# MK-312BT_V1_3B.net
KiCad netlist of a schematic drawn in EAGLE
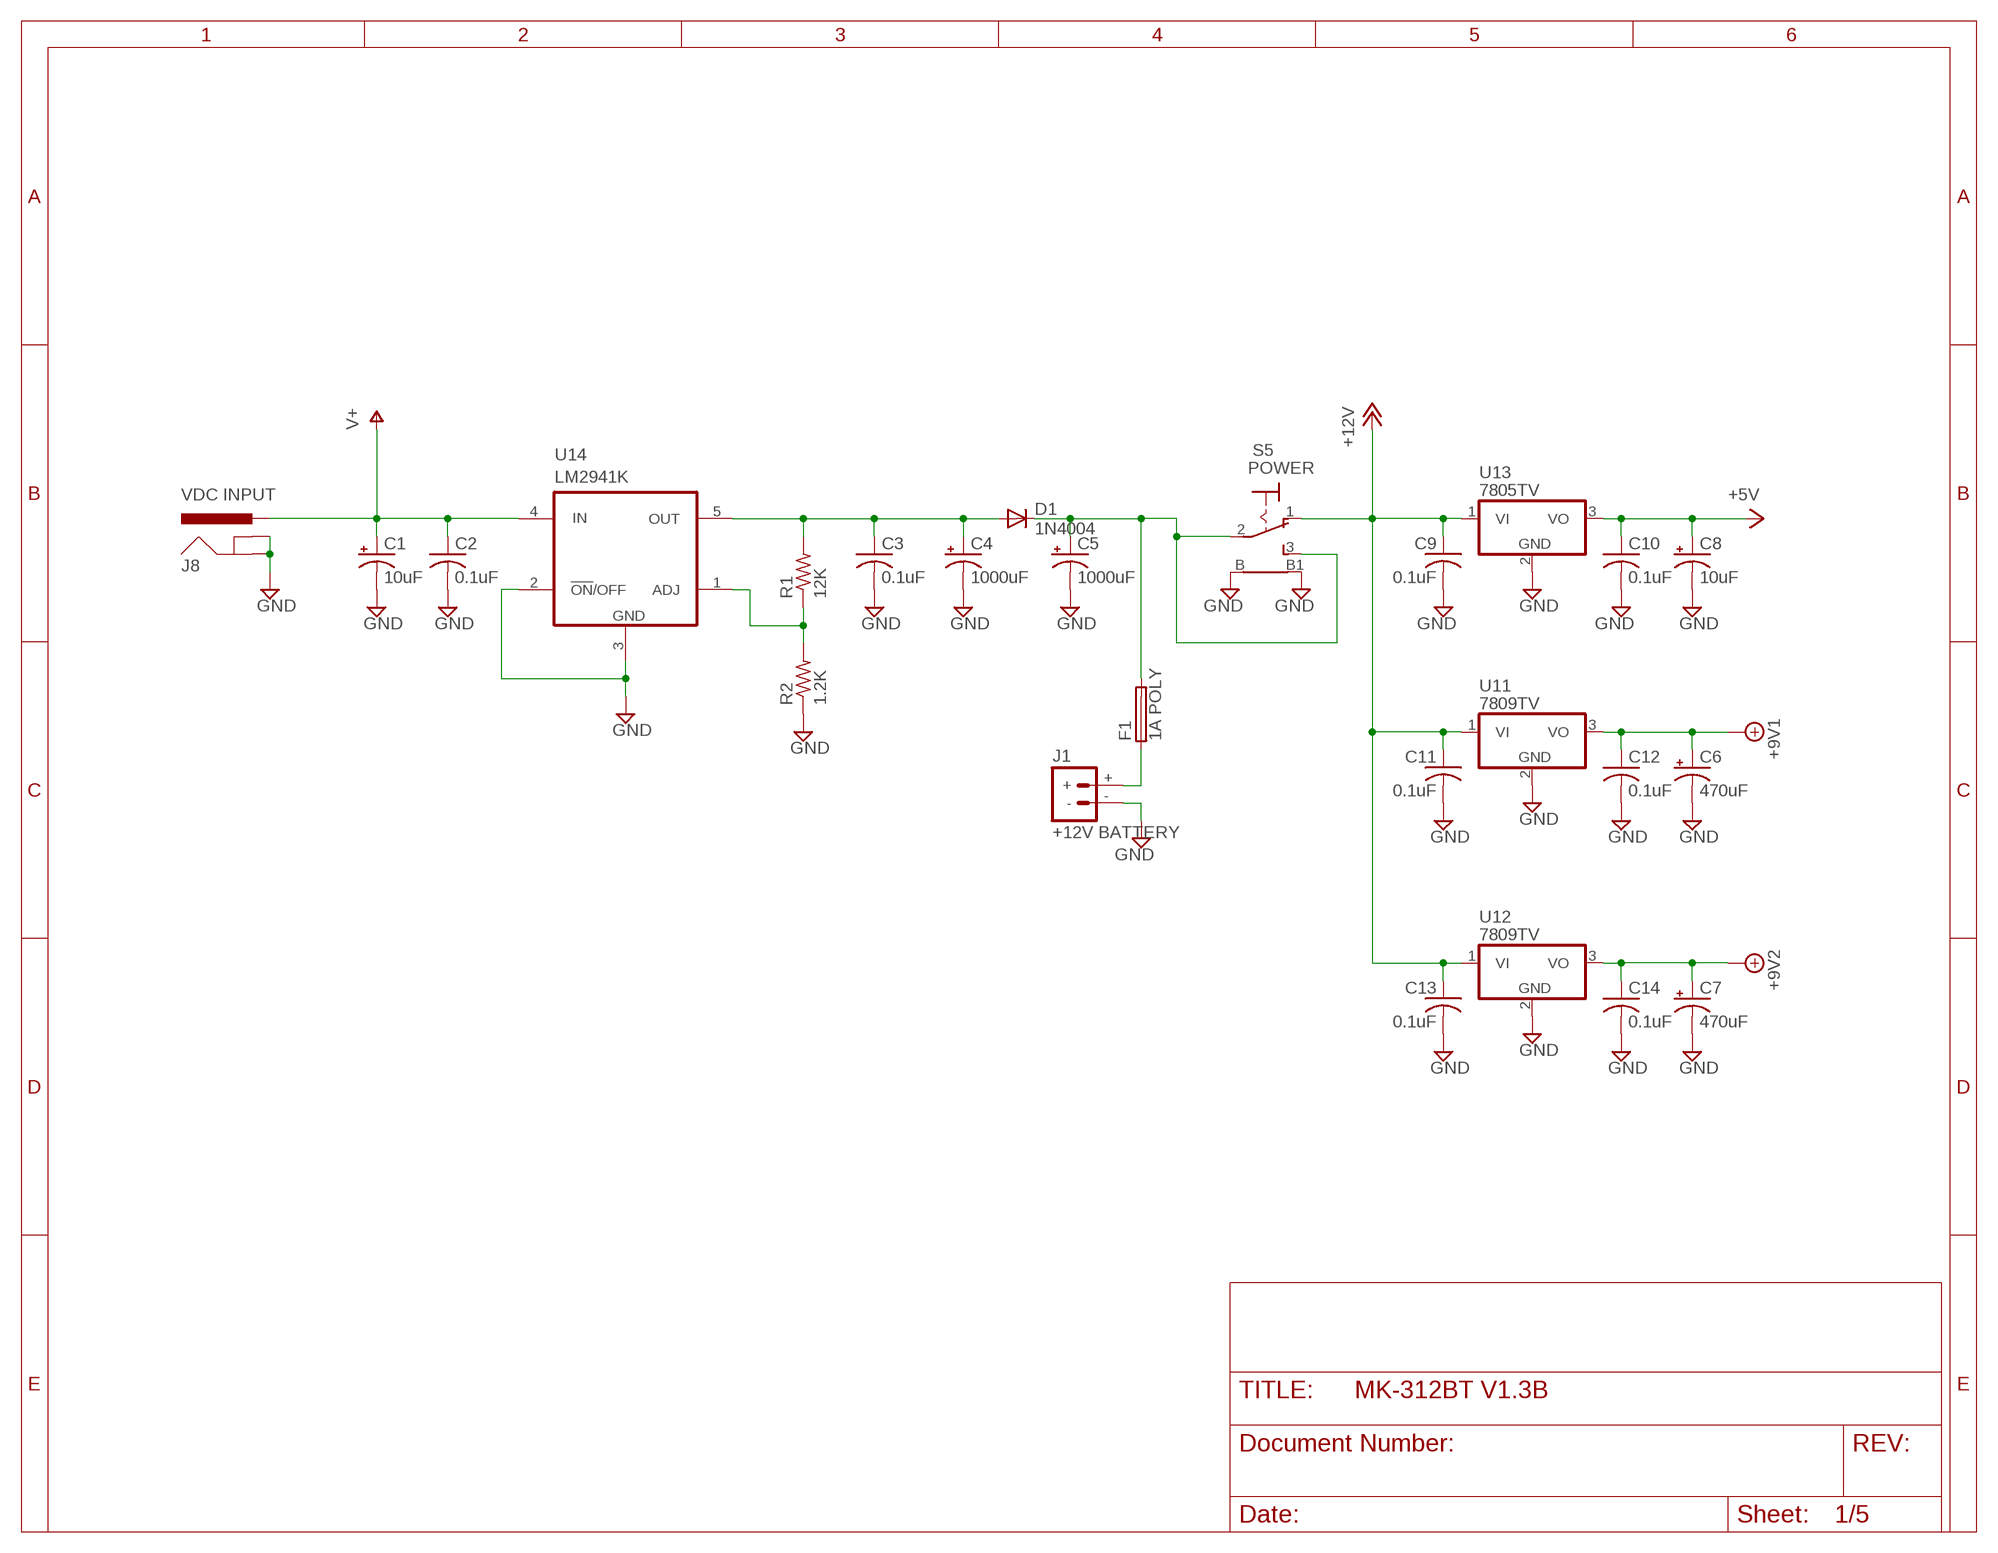
[diagram p0: schematic, sheet 1]
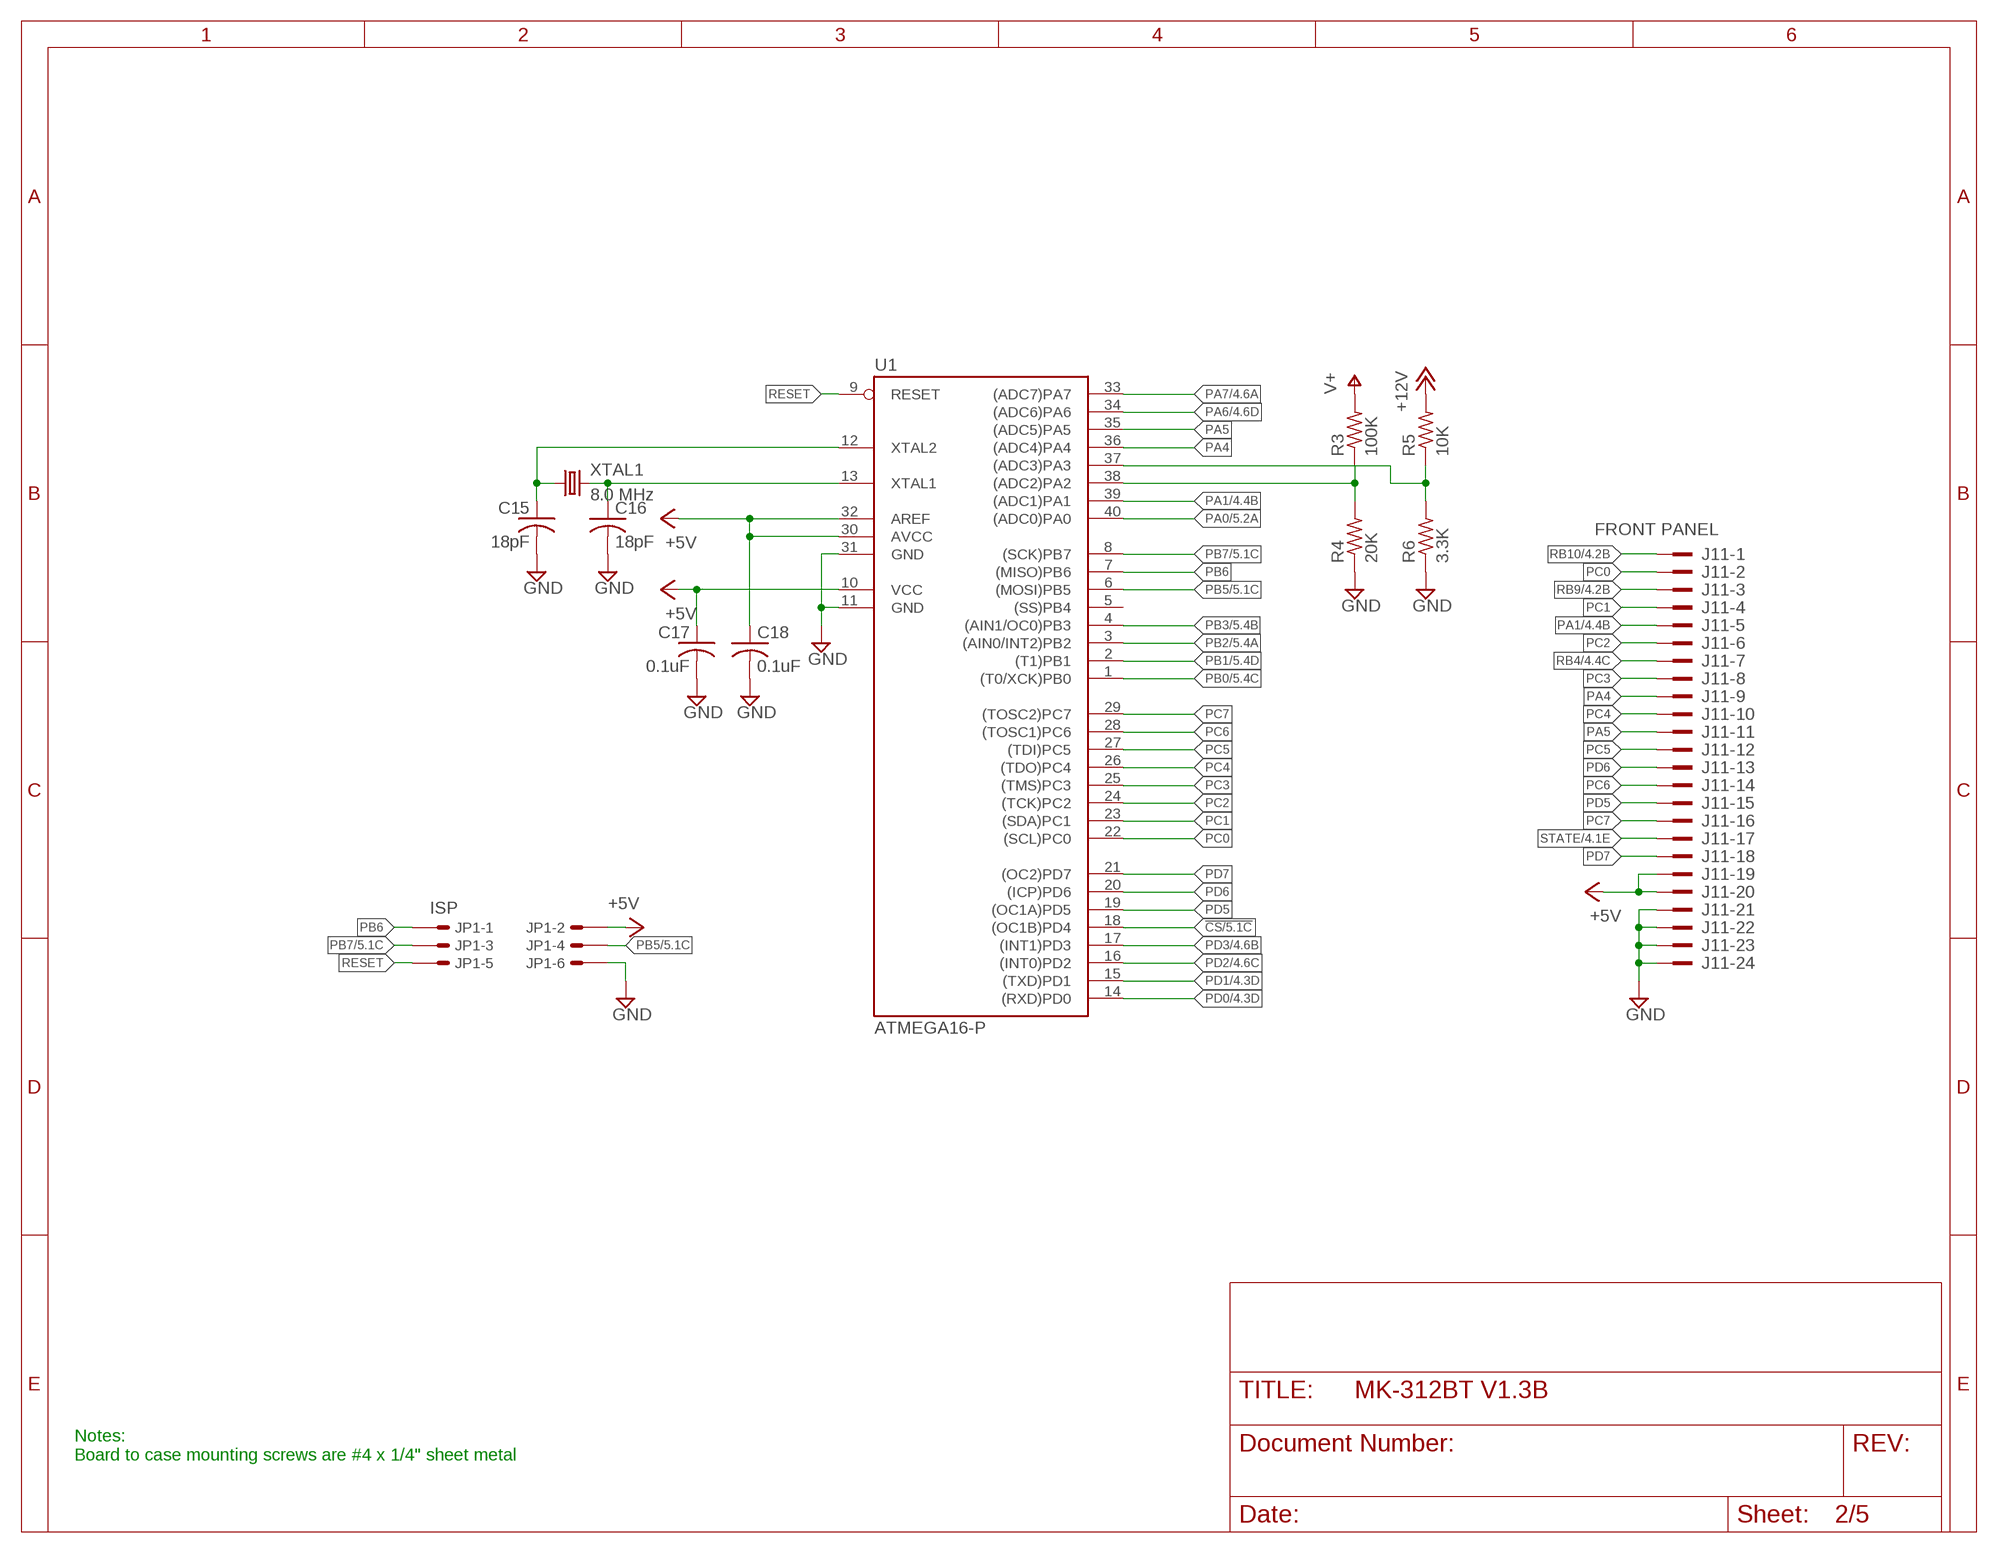
[diagram p1: schematic, sheet 2]
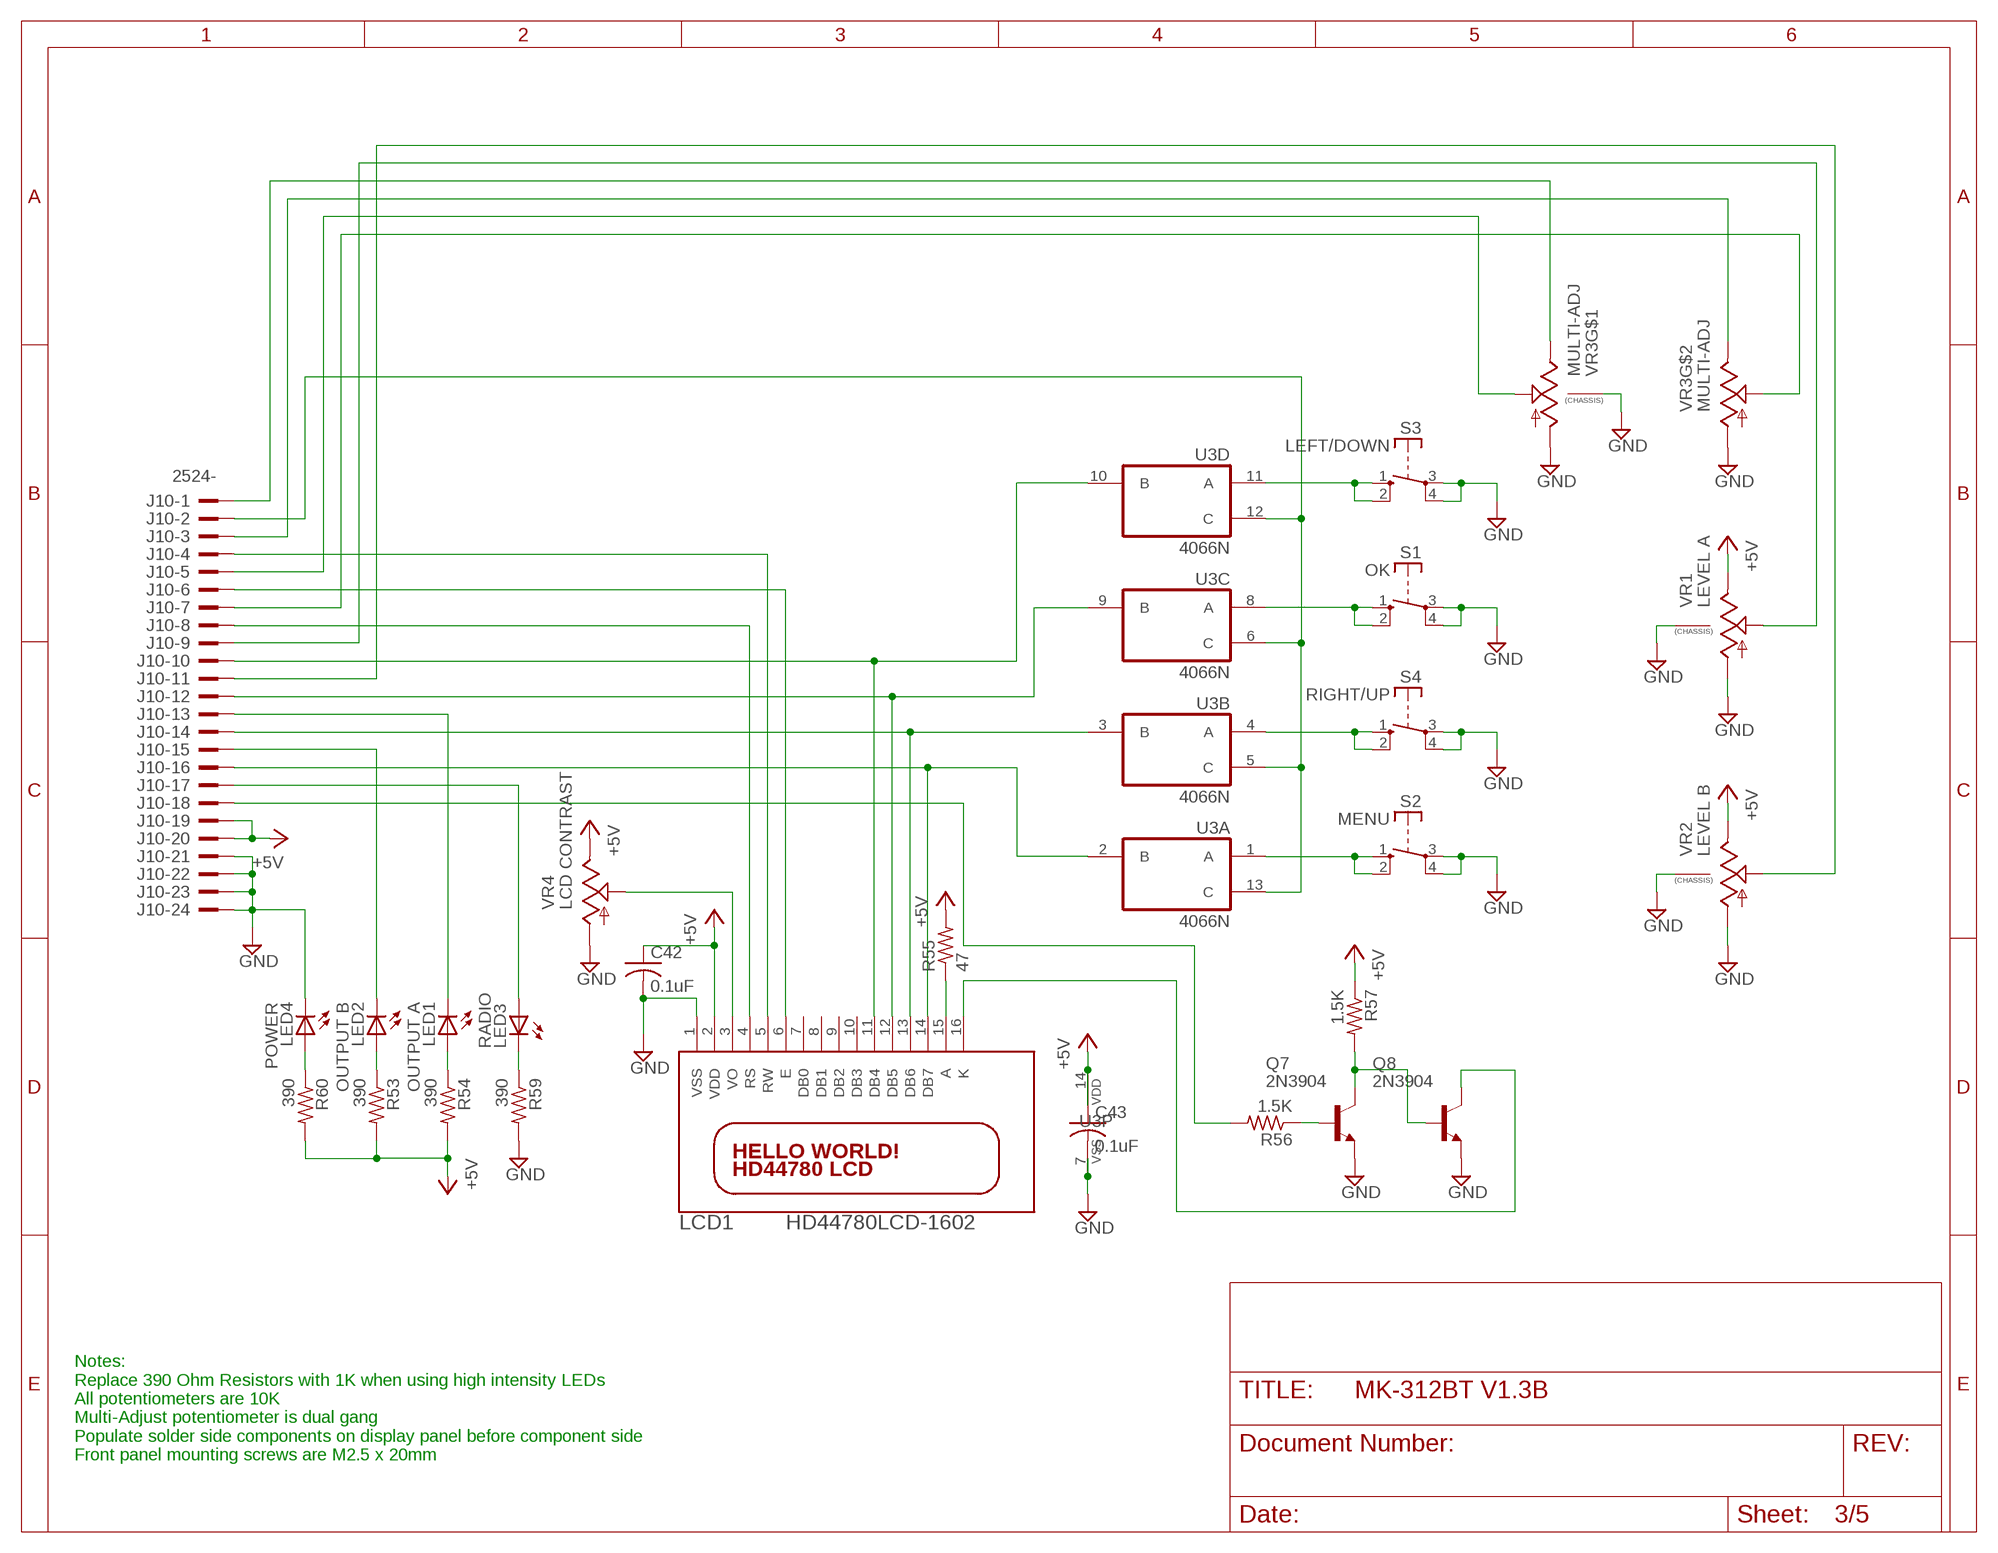
[diagram p2: schematic, sheet 3]
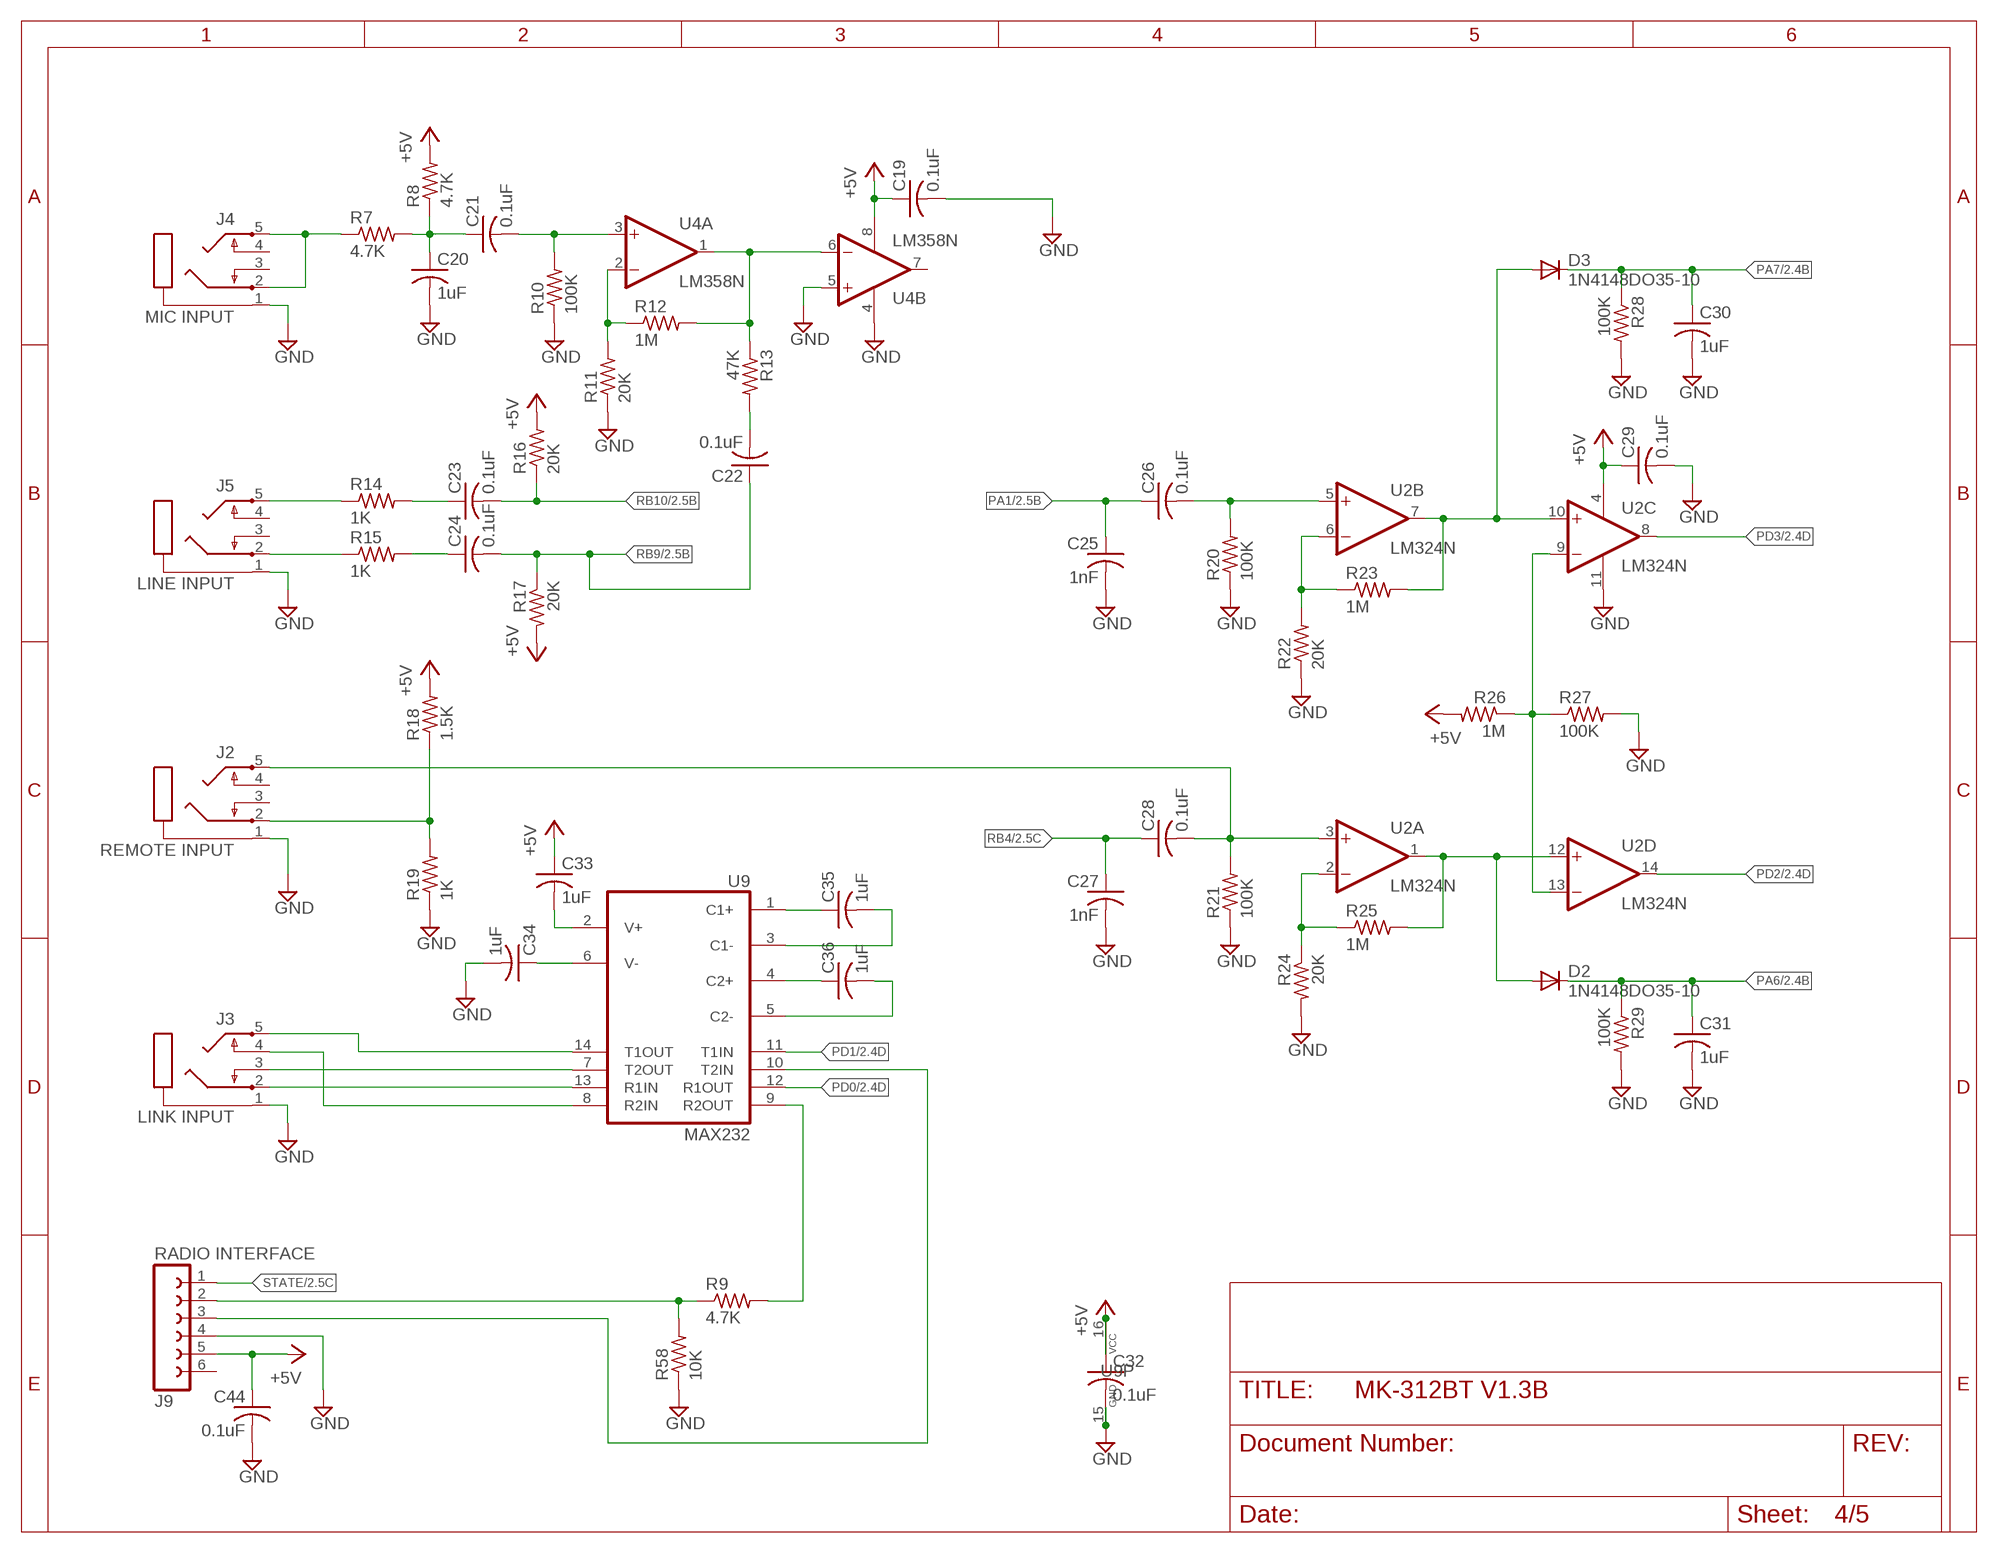
[diagram p3: schematic, sheet 4]
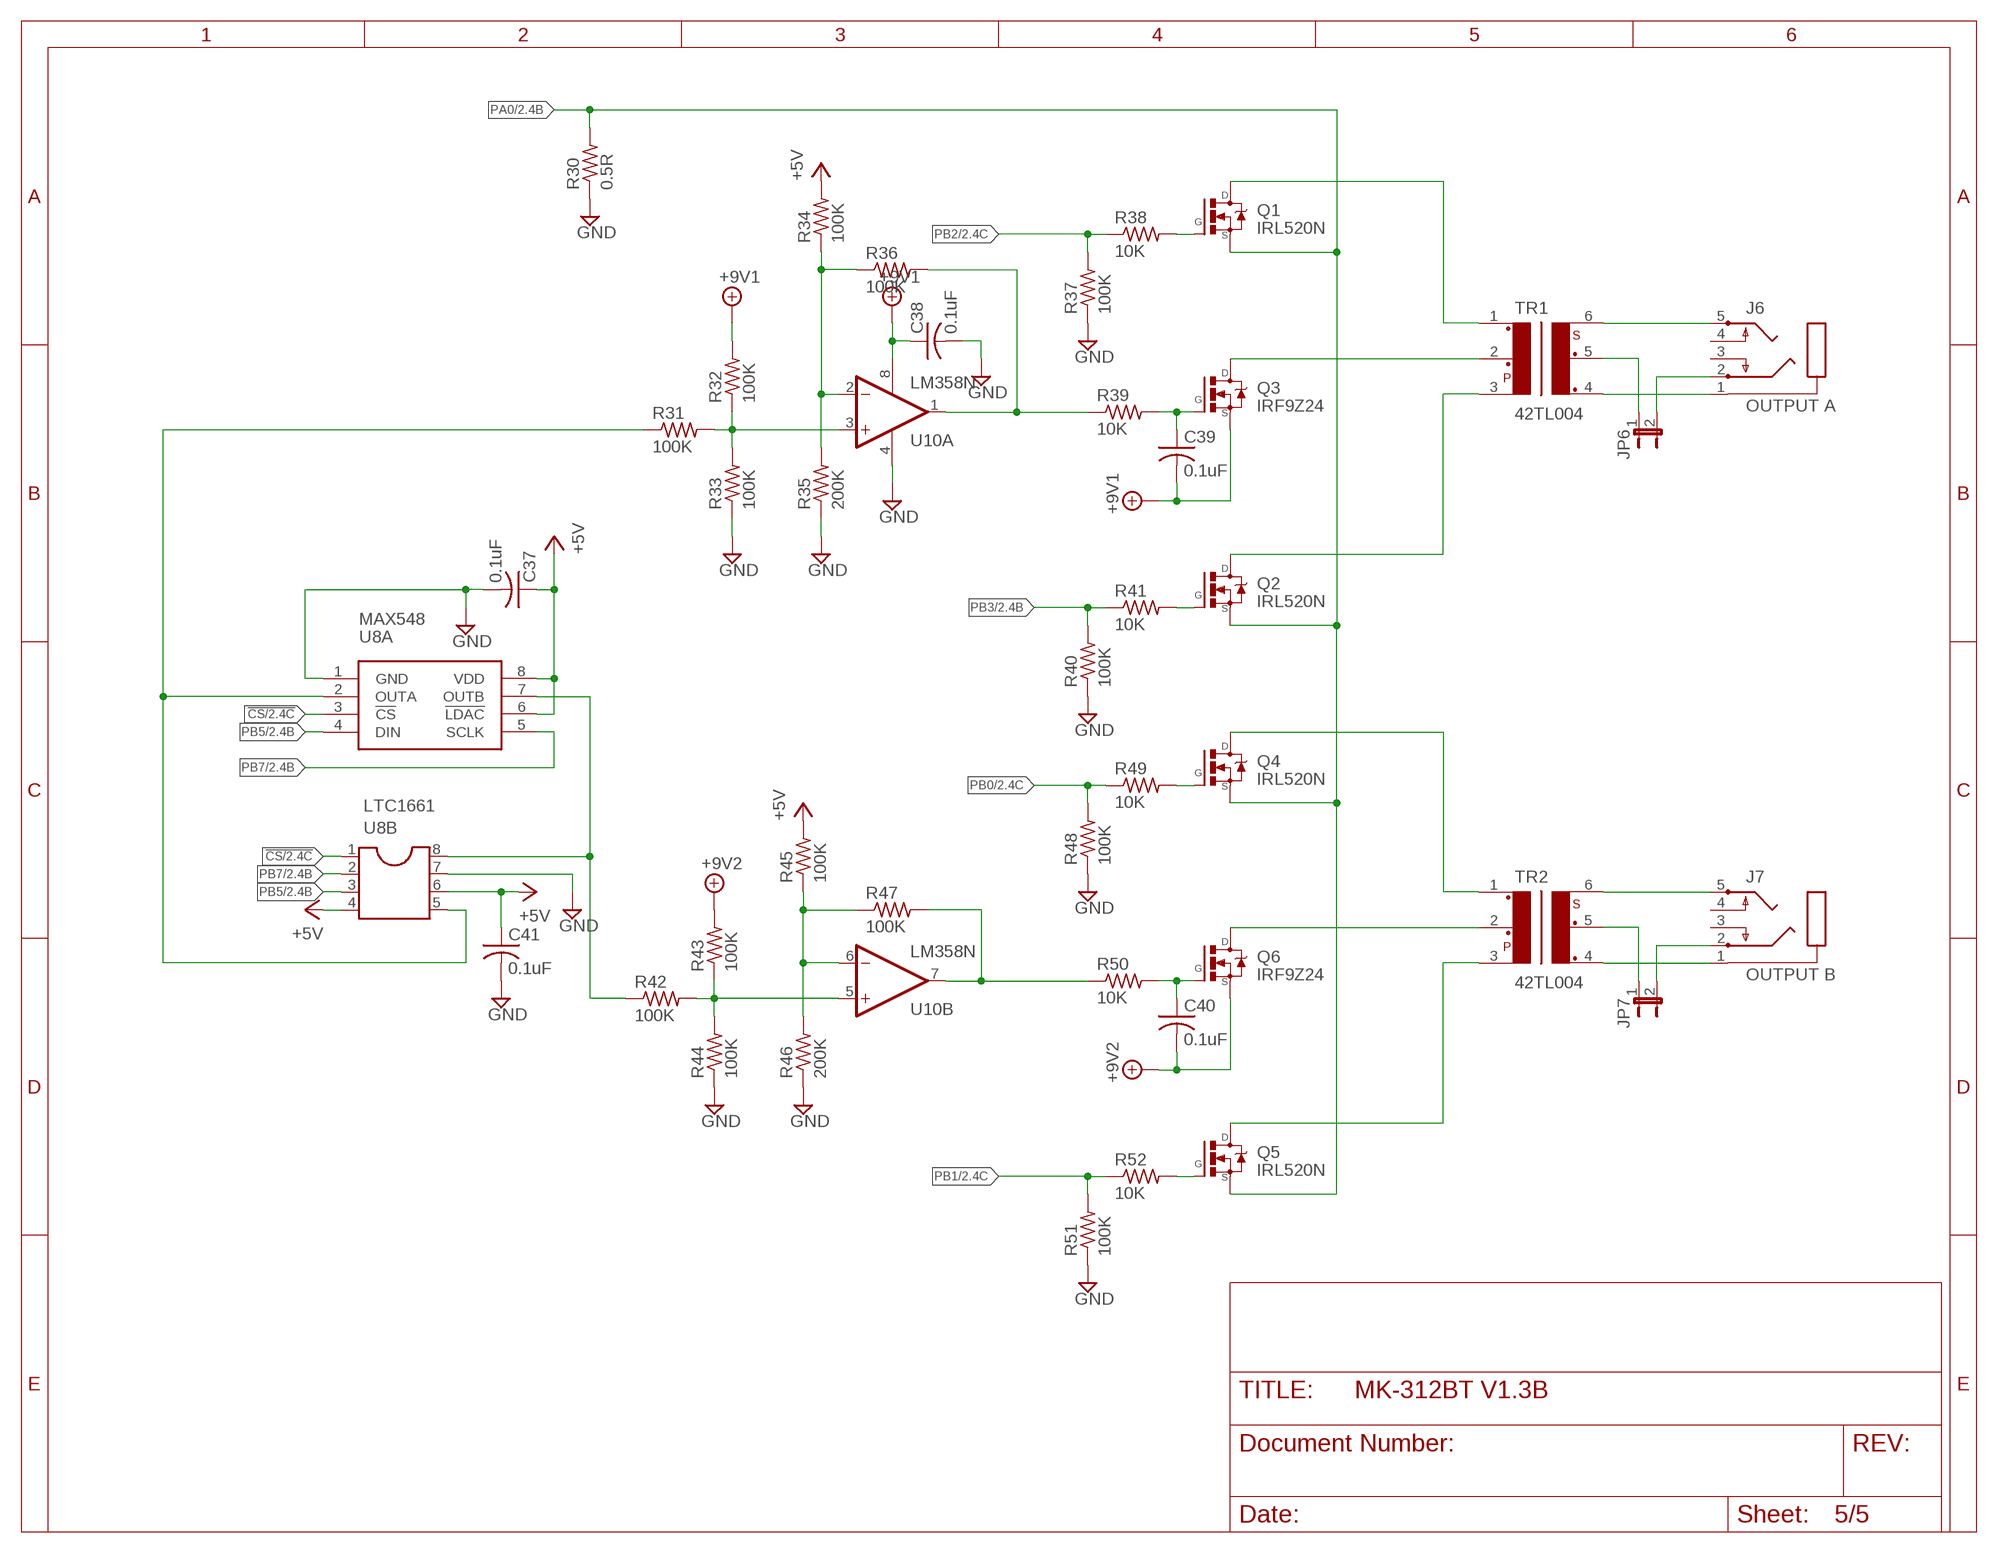
[diagram p4: schematic, sheet 5]

(export (version "E")
  (design (tool "Eeschema 10.0.6"))
  (components
    (comp (ref "C15")
      (value "18pF")
      (footprint "eagle-import:C025-024X044")
      (libsource (lib "eagle-import") (part "C-US025-024X044"))
    )
    (comp (ref "C16")
      (value "18pF")
      (footprint "eagle-import:C025-024X044")
      (libsource (lib "eagle-import") (part "C-US025-024X044"))
    )
    (comp (ref "C17")
      (value "0.1uF")
      (footprint "eagle-import:C025-024X044")
      (libsource (lib "eagle-import") (part "C-US025-024X044"))
    )
    (comp (ref "C18")
      (value "0.1uF")
      (footprint "eagle-import:C025-024X044")
      (libsource (lib "eagle-import") (part "C-US025-024X044"))
    )
    (comp (ref "J11")
      (value "FRONT PANEL")
      (footprint "eagle-import:PAK100_2500-24")
      (libsource (lib "eagle-import") (part "2524-"))
    )
    (comp (ref "JP1")
      (value "ISP")
      (footprint "eagle-import:057-006-1")
      (libsource (lib "eagle-import") (part "057-006-1"))
    )
    (comp (ref "R3")
      (value "100K")
      (footprint "eagle-import:0207_10")
      (libsource (lib "eagle-import") (part "R-US_0207/10"))
    )
    (comp (ref "R4")
      (value "20K")
      (footprint "eagle-import:0207_10")
      (libsource (lib "eagle-import") (part "R-US_0207/10"))
    )
    (comp (ref "R5")
      (value "10K")
      (footprint "eagle-import:0207_10")
      (libsource (lib "eagle-import") (part "R-US_0207/10"))
    )
    (comp (ref "R6")
      (value "3.3K")
      (footprint "eagle-import:0207_10")
      (libsource (lib "eagle-import") (part "R-US_0207/10"))
    )
    (comp (ref "U1")
      (value "ATMEGA16-P")
      (footprint "eagle-import:DIL40")
      (fields (field (name "MPN") "ATMEGA16-16PU"))
      (libsource (lib "eagle-import") (part "MEGA16-P"))
    )
    (comp (ref "XTAL1")
      (value "8.0 MHz")
      (footprint "eagle-import:HC49_S")
      (libsource (lib "eagle-import") (part "CRYSTALHC49S"))
    )
    (comp (ref "C37")
      (value "0.1uF")
      (footprint "eagle-import:C025-024X044")
      (libsource (lib "eagle-import") (part "C-US025-024X044"))
    )
    (comp (ref "C38")
      (value "0.1uF")
      (footprint "eagle-import:C025-024X044")
      (libsource (lib "eagle-import") (part "C-US025-024X044"))
    )
    (comp (ref "C39")
      (value "0.1uF")
      (footprint "eagle-import:C025-024X044")
      (libsource (lib "eagle-import") (part "C-US025-024X044"))
    )
    (comp (ref "C40")
      (value "0.1uF")
      (footprint "eagle-import:C025-024X044")
      (libsource (lib "eagle-import") (part "C-US025-024X044"))
    )
    (comp (ref "C41")
      (value "0.1uF")
      (footprint "eagle-import:C025-024X044")
      (libsource (lib "eagle-import") (part "C-US025-024X044"))
    )
    (comp (ref "J6")
      (value "OUTPUT A")
      (footprint "eagle-import:STX3100")
      (libsource (lib "eagle-import") (part "STEREOJACK"))
    )
    (comp (ref "J7")
      (value "OUTPUT B")
      (footprint "eagle-import:STX3100")
      (libsource (lib "eagle-import") (part "STEREOJACK"))
    )
    (comp (ref "JP6")
      (value "JP1E")
      (footprint "eagle-import:JP1")
      (libsource (lib "eagle-import") (part "JP1E"))
    )
    (comp (ref "JP7")
      (value "JP1E")
      (footprint "eagle-import:JP1")
      (libsource (lib "eagle-import") (part "JP1E"))
    )
    (comp (ref "Q1")
      (value "IRL520N")
      (footprint "eagle-import:TO220V")
      (libsource (lib "eagle-import") (part "IRL530N-V"))
    )
    (comp (ref "Q2")
      (value "IRL520N")
      (footprint "eagle-import:TO220V")
      (libsource (lib "eagle-import") (part "IRL530N-V"))
    )
    (comp (ref "Q3")
      (value "IRF9Z24")
      (footprint "eagle-import:TO220V")
      (libsource (lib "eagle-import") (part "IRL530N-V"))
    )
    (comp (ref "Q4")
      (value "IRL520N")
      (footprint "eagle-import:TO220V")
      (libsource (lib "eagle-import") (part "IRL530N-V"))
    )
    (comp (ref "Q5")
      (value "IRL520N")
      (footprint "eagle-import:TO220V")
      (libsource (lib "eagle-import") (part "IRL530N-V"))
    )
    (comp (ref "Q6")
      (value "IRF9Z24")
      (footprint "eagle-import:TO220V")
      (libsource (lib "eagle-import") (part "IRL530N-V"))
    )
    (comp (ref "R30")
      (value "0.5R")
      (footprint "eagle-import:0309_12")
      (libsource (lib "eagle-import") (part "R-US_0309/12"))
    )
    (comp (ref "R31")
      (value "100K")
      (footprint "eagle-import:0207_10")
      (libsource (lib "eagle-import") (part "R-US_0207/10"))
    )
    (comp (ref "R32")
      (value "100K")
      (footprint "eagle-import:0207_10")
      (libsource (lib "eagle-import") (part "R-US_0207/10"))
    )
    (comp (ref "R33")
      (value "100K")
      (footprint "eagle-import:0207_10")
      (libsource (lib "eagle-import") (part "R-US_0207/10"))
    )
    (comp (ref "R34")
      (value "100K")
      (footprint "eagle-import:0207_10")
      (libsource (lib "eagle-import") (part "R-US_0207/10"))
    )
    (comp (ref "R35")
      (value "200K")
      (footprint "eagle-import:0207_10")
      (libsource (lib "eagle-import") (part "R-US_0207/10"))
    )
    (comp (ref "R36")
      (value "100K")
      (footprint "eagle-import:0207_10")
      (libsource (lib "eagle-import") (part "R-US_0207/10"))
    )
    (comp (ref "R37")
      (value "100K")
      (footprint "eagle-import:0207_10")
      (libsource (lib "eagle-import") (part "R-US_0207/10"))
    )
    (comp (ref "R38")
      (value "10K")
      (footprint "eagle-import:0207_10")
      (libsource (lib "eagle-import") (part "R-US_0207/10"))
    )
    (comp (ref "R39")
      (value "10K")
      (footprint "eagle-import:0207_10")
      (libsource (lib "eagle-import") (part "R-US_0207/10"))
    )
    (comp (ref "R40")
      (value "100K")
      (footprint "eagle-import:0207_10")
      (libsource (lib "eagle-import") (part "R-US_0207/10"))
    )
    (comp (ref "R41")
      (value "10K")
      (footprint "eagle-import:0207_10")
      (libsource (lib "eagle-import") (part "R-US_0207/10"))
    )
    (comp (ref "R42")
      (value "100K")
      (footprint "eagle-import:0207_10")
      (libsource (lib "eagle-import") (part "R-US_0207/10"))
    )
    (comp (ref "R43")
      (value "100K")
      (footprint "eagle-import:0207_10")
      (libsource (lib "eagle-import") (part "R-US_0207/10"))
    )
    (comp (ref "R44")
      (value "100K")
      (footprint "eagle-import:0207_10")
      (libsource (lib "eagle-import") (part "R-US_0207/10"))
    )
    (comp (ref "R45")
      (value "100K")
      (footprint "eagle-import:0207_10")
      (libsource (lib "eagle-import") (part "R-US_0207/10"))
    )
    (comp (ref "R46")
      (value "200K")
      (footprint "eagle-import:0207_10")
      (libsource (lib "eagle-import") (part "R-US_0207/10"))
    )
    (comp (ref "R47")
      (value "100K")
      (footprint "eagle-import:0207_10")
      (libsource (lib "eagle-import") (part "R-US_0207/10"))
    )
    (comp (ref "R48")
      (value "100K")
      (footprint "eagle-import:0207_10")
      (libsource (lib "eagle-import") (part "R-US_0207/10"))
    )
    (comp (ref "R49")
      (value "10K")
      (footprint "eagle-import:0207_10")
      (libsource (lib "eagle-import") (part "R-US_0207/10"))
    )
    (comp (ref "R50")
      (value "10K")
      (footprint "eagle-import:0207_10")
      (libsource (lib "eagle-import") (part "R-US_0207/10"))
    )
    (comp (ref "R51")
      (value "100K")
      (footprint "eagle-import:0207_10")
      (libsource (lib "eagle-import") (part "R-US_0207/10"))
    )
    (comp (ref "R52")
      (value "10K")
      (footprint "eagle-import:0207_10")
      (libsource (lib "eagle-import") (part "R-US_0207/10"))
    )
    (comp (ref "TR1")
      (value "42TL004")
      (footprint "eagle-import:42TL")
      (libsource (lib "eagle-import") (part "42T?L023"))
    )
    (comp (ref "TR2")
      (value "42TL004")
      (footprint "eagle-import:42TL")
      (libsource (lib "eagle-import") (part "42T?L023"))
    )
    (comp (ref "U8A")
      (value "MAX548")
      (footprint "eagle-import:DIL08")
      (libsource (lib "eagle-import") (part "MAX548"))
    )
    (comp (ref "U8B")
      (value "LTC1661")
      (footprint "eagle-import:SOCKET-08")
      (libsource (lib "eagle-import") (part "DIL8S"))
    )
    (comp (ref "U10")
      (value "LM358N")
      (footprint "eagle-import:DIL08")
      (libsource (lib "eagle-import") (part "LM358N"))
    )
    (comp (ref "C19")
      (value "0.1uF")
      (footprint "eagle-import:C025-024X044")
      (libsource (lib "eagle-import") (part "C-US025-024X044"))
    )
    (comp (ref "C20")
      (value "1uF")
      (footprint "eagle-import:C025-024X044")
      (libsource (lib "eagle-import") (part "C-US025-024X044"))
    )
    (comp (ref "C21")
      (value "0.1uF")
      (footprint "eagle-import:C025-024X044")
      (libsource (lib "eagle-import") (part "C-US025-024X044"))
    )
    (comp (ref "C22")
      (value "0.1uF")
      (footprint "eagle-import:C025-024X044")
      (libsource (lib "eagle-import") (part "C-US025-024X044"))
    )
    (comp (ref "C23")
      (value "0.1uF")
      (footprint "eagle-import:C025-024X044")
      (libsource (lib "eagle-import") (part "C-US025-024X044"))
    )
    (comp (ref "C24")
      (value "0.1uF")
      (footprint "eagle-import:C025-024X044")
      (libsource (lib "eagle-import") (part "C-US025-024X044"))
    )
    (comp (ref "C25")
      (value "1nF")
      (footprint "eagle-import:C025-024X044")
      (libsource (lib "eagle-import") (part "C-US025-024X044"))
    )
    (comp (ref "C26")
      (value "0.1uF")
      (footprint "eagle-import:C025-024X044")
      (libsource (lib "eagle-import") (part "C-US025-024X044"))
    )
    (comp (ref "C27")
      (value "1nF")
      (footprint "eagle-import:C025-024X044")
      (libsource (lib "eagle-import") (part "C-US025-024X044"))
    )
    (comp (ref "C28")
      (value "0.1uF")
      (footprint "eagle-import:C025-024X044")
      (libsource (lib "eagle-import") (part "C-US025-024X044"))
    )
    (comp (ref "C29")
      (value "0.1uF")
      (footprint "eagle-import:C025-024X044")
      (libsource (lib "eagle-import") (part "C-US025-024X044"))
    )
    (comp (ref "C30")
      (value "1uF")
      (footprint "eagle-import:C025-024X044")
      (libsource (lib "eagle-import") (part "C-US025-024X044"))
    )
    (comp (ref "C31")
      (value "1uF")
      (footprint "eagle-import:C025-024X044")
      (libsource (lib "eagle-import") (part "C-US025-024X044"))
    )
    (comp (ref "C32")
      (value "0.1uF")
      (footprint "eagle-import:C025-024X044")
      (libsource (lib "eagle-import") (part "C-US025-024X044"))
    )
    (comp (ref "C33")
      (value "1uF")
      (footprint "eagle-import:C025-024X044")
      (libsource (lib "eagle-import") (part "C-US025-024X044"))
    )
    (comp (ref "C34")
      (value "1uF")
      (footprint "eagle-import:C025-024X044")
      (libsource (lib "eagle-import") (part "C-US025-024X044"))
    )
    (comp (ref "C35")
      (value "1uF")
      (footprint "eagle-import:C025-024X044")
      (libsource (lib "eagle-import") (part "C-US025-024X044"))
    )
    (comp (ref "C36")
      (value "1uF")
      (footprint "eagle-import:C025-024X044")
      (libsource (lib "eagle-import") (part "C-US025-024X044"))
    )
    (comp (ref "C44")
      (value "0.1uF")
      (footprint "eagle-import:C025-024X044")
      (libsource (lib "eagle-import") (part "C-US025-024X044"))
    )
    (comp (ref "D2")
      (value "1N4148DO35-10")
      (footprint "eagle-import:DO35-10")
      (libsource (lib "eagle-import") (part "1N4148DO35-10"))
    )
    (comp (ref "D3")
      (value "1N4148DO35-10")
      (footprint "eagle-import:DO35-10")
      (libsource (lib "eagle-import") (part "1N4148DO35-10"))
    )
    (comp (ref "J2")
      (value "REMOTE INPUT")
      (footprint "eagle-import:STX3100")
      (libsource (lib "eagle-import") (part "STEREOJACK"))
    )
    (comp (ref "J3")
      (value "LINK INPUT")
      (footprint "eagle-import:STX3100")
      (libsource (lib "eagle-import") (part "STEREOJACK"))
    )
    (comp (ref "J4")
      (value "MIC INPUT")
      (footprint "eagle-import:STX3100")
      (libsource (lib "eagle-import") (part "STEREOJACK"))
    )
    (comp (ref "J5")
      (value "LINE INPUT")
      (footprint "eagle-import:STX3100")
      (libsource (lib "eagle-import") (part "STEREOJACK"))
    )
    (comp (ref "J9")
      (value "RADIO INTERFACE")
      (footprint "eagle-import:FE06")
      (libsource (lib "eagle-import") (part "FE06-1"))
    )
    (comp (ref "R7")
      (value "4.7K")
      (footprint "eagle-import:0207_10")
      (libsource (lib "eagle-import") (part "R-US_0207/10"))
    )
    (comp (ref "R8")
      (value "4.7K")
      (footprint "eagle-import:0207_10")
      (libsource (lib "eagle-import") (part "R-US_0207/10"))
    )
    (comp (ref "R9")
      (value "4.7K")
      (footprint "eagle-import:0207_10")
      (libsource (lib "eagle-import") (part "R-US_0207/10"))
    )
    (comp (ref "R10")
      (value "100K")
      (footprint "eagle-import:0207_10")
      (libsource (lib "eagle-import") (part "R-US_0207/10"))
    )
    (comp (ref "R11")
      (value "20K")
      (footprint "eagle-import:0207_10")
      (libsource (lib "eagle-import") (part "R-US_0207/10"))
    )
    (comp (ref "R12")
      (value "1M")
      (footprint "eagle-import:0207_10")
      (libsource (lib "eagle-import") (part "R-US_0207/10"))
    )
    (comp (ref "R13")
      (value "47K")
      (footprint "eagle-import:0207_10")
      (libsource (lib "eagle-import") (part "R-US_0207/10"))
    )
    (comp (ref "R14")
      (value "1K")
      (footprint "eagle-import:0207_10")
      (libsource (lib "eagle-import") (part "R-US_0207/10"))
    )
    (comp (ref "R15")
      (value "1K")
      (footprint "eagle-import:0207_10")
      (libsource (lib "eagle-import") (part "R-US_0207/10"))
    )
    (comp (ref "R16")
      (value "20K")
      (footprint "eagle-import:0207_10")
      (libsource (lib "eagle-import") (part "R-US_0207/10"))
    )
    (comp (ref "R17")
      (value "20K")
      (footprint "eagle-import:0207_10")
      (libsource (lib "eagle-import") (part "R-US_0207/10"))
    )
    (comp (ref "R18")
      (value "1.5K")
      (footprint "eagle-import:0207_10")
      (libsource (lib "eagle-import") (part "R-US_0207/10"))
    )
    (comp (ref "R19")
      (value "1K")
      (footprint "eagle-import:0207_10")
      (libsource (lib "eagle-import") (part "R-US_0207/10"))
    )
    (comp (ref "R20")
      (value "100K")
      (footprint "eagle-import:0207_10")
      (libsource (lib "eagle-import") (part "R-US_0207/10"))
    )
    (comp (ref "R21")
      (value "100K")
      (footprint "eagle-import:0207_10")
      (libsource (lib "eagle-import") (part "R-US_0207/10"))
    )
    (comp (ref "R22")
      (value "20K")
      (footprint "eagle-import:0207_10")
      (libsource (lib "eagle-import") (part "R-US_0207/10"))
    )
    (comp (ref "R23")
      (value "1M")
      (footprint "eagle-import:0207_10")
      (libsource (lib "eagle-import") (part "R-US_0207/10"))
    )
    (comp (ref "R24")
      (value "20K")
      (footprint "eagle-import:0207_10")
      (libsource (lib "eagle-import") (part "R-US_0207/10"))
    )
    (comp (ref "R25")
      (value "1M")
      (footprint "eagle-import:0207_10")
      (libsource (lib "eagle-import") (part "R-US_0207/10"))
    )
    (comp (ref "R26")
      (value "1M")
      (footprint "eagle-import:0207_10")
      (libsource (lib "eagle-import") (part "R-US_0207/10"))
    )
    (comp (ref "R27")
      (value "100K")
      (footprint "eagle-import:0207_10")
      (libsource (lib "eagle-import") (part "R-US_0207/10"))
    )
    (comp (ref "R28")
      (value "100K")
      (footprint "eagle-import:0207_10")
      (libsource (lib "eagle-import") (part "R-US_0207/10"))
    )
    (comp (ref "R29")
      (value "100K")
      (footprint "eagle-import:0207_10")
      (libsource (lib "eagle-import") (part "R-US_0207/10"))
    )
    (comp (ref "R58")
      (value "10K")
      (footprint "eagle-import:0207_10")
      (libsource (lib "eagle-import") (part "R-US_0207/10"))
    )
    (comp (ref "U2")
      (value "LM324N")
      (footprint "eagle-import:DIL14")
      (libsource (lib "eagle-import") (part "LM324N"))
    )
    (comp (ref "U4")
      (value "LM358N")
      (footprint "eagle-import:DIL08")
      (libsource (lib "eagle-import") (part "LM358N"))
    )
    (comp (ref "U9")
      (value "MAX232")
      (footprint "eagle-import:DIL16")
      (fields (field (name "MF") "MAXIM") (field (name "MPN") "MAX232ACPE+"))
      (libsource (lib "eagle-import") (part "MAX232"))
    )
    (comp (ref "C1")
      (value "10uF")
      (footprint "eagle-import:E2,5-7")
      (libsource (lib "eagle-import") (part "CPOL-USE2.5-7"))
    )
    (comp (ref "C2")
      (value "0.1uF")
      (footprint "eagle-import:C025-024X044")
      (libsource (lib "eagle-import") (part "C-US025-024X044"))
    )
    (comp (ref "C3")
      (value "0.1uF")
      (footprint "eagle-import:C025-024X044")
      (libsource (lib "eagle-import") (part "C-US025-024X044"))
    )
    (comp (ref "C4")
      (value "1000uF")
      (footprint "eagle-import:E5-10,5")
      (libsource (lib "eagle-import") (part "CPOL-USE5-10.5"))
    )
    (comp (ref "C5")
      (value "1000uF")
      (footprint "eagle-import:E5-10,5")
      (libsource (lib "eagle-import") (part "CPOL-USE5-10.5"))
    )
    (comp (ref "C6")
      (value "470uF")
      (footprint "eagle-import:E3,5-8")
      (libsource (lib "eagle-import") (part "CPOL-USE3.5-8"))
    )
    (comp (ref "C7")
      (value "470uF")
      (footprint "eagle-import:E3,5-8")
      (libsource (lib "eagle-import") (part "CPOL-USE3.5-8"))
    )
    (comp (ref "C8")
      (value "10uF")
      (footprint "eagle-import:E2,5-7")
      (libsource (lib "eagle-import") (part "CPOL-USE2.5-7"))
    )
    (comp (ref "C9")
      (value "0.1uF")
      (footprint "eagle-import:C025-024X044")
      (libsource (lib "eagle-import") (part "C-US025-024X044"))
    )
    (comp (ref "C10")
      (value "0.1uF")
      (footprint "eagle-import:C025-024X044")
      (libsource (lib "eagle-import") (part "C-US025-024X044"))
    )
    (comp (ref "C11")
      (value "0.1uF")
      (footprint "eagle-import:C025-024X044")
      (libsource (lib "eagle-import") (part "C-US025-024X044"))
    )
    (comp (ref "C12")
      (value "0.1uF")
      (footprint "eagle-import:C025-024X044")
      (libsource (lib "eagle-import") (part "C-US025-024X044"))
    )
    (comp (ref "C13")
      (value "0.1uF")
      (footprint "eagle-import:C025-024X044")
      (libsource (lib "eagle-import") (part "C-US025-024X044"))
    )
    (comp (ref "C14")
      (value "0.1uF")
      (footprint "eagle-import:C025-024X044")
      (libsource (lib "eagle-import") (part "C-US025-024X044"))
    )
    (comp (ref "D1")
      (value "1N4004")
      (footprint "eagle-import:DO41-10")
      (libsource (lib "eagle-import") (part "1N4004"))
    )
    (comp (ref "F1")
      (value "1A POLY")
      (footprint "eagle-import:LITTLEFUSE")
      (libsource (lib "eagle-import") (part "LITTLEFUSE"))
    )
    (comp (ref "J1")
      (value "+12V BATTERY")
      (footprint "eagle-import:DEANS")
      (libsource (lib "eagle-import") (part "BATTERY_CONNDEANS"))
    )
    (comp (ref "J8")
      (value "VDC INPUT")
      (footprint "eagle-import:POWER_JACK_SLOT")
      (libsource (lib "eagle-import") (part "POWER_JACKSLT"))
    )
    (comp (ref "R1")
      (value "12K")
      (footprint "eagle-import:0207_10")
      (libsource (lib "eagle-import") (part "R-US_0207/10"))
    )
    (comp (ref "R2")
      (value "1.2K")
      (footprint "eagle-import:0207_10")
      (libsource (lib "eagle-import") (part "R-US_0207/10"))
    )
    (comp (ref "S5")
      (value "POWER")
      (footprint "eagle-import:LPV-1")
      (libsource (lib "eagle-import") (part "LPV-1"))
    )
    (comp (ref "U11")
      (value "7809TV")
      (footprint "eagle-import:TO220V")
      (libsource (lib "eagle-import") (part "78TV05"))
    )
    (comp (ref "U12")
      (value "7809TV")
      (footprint "eagle-import:TO220V")
      (libsource (lib "eagle-import") (part "78TV05"))
    )
    (comp (ref "U13")
      (value "7805TV")
      (footprint "eagle-import:TO220V")
      (libsource (lib "eagle-import") (part "78TV05"))
    )
    (comp (ref "U14")
      (value "LM2941K")
      (footprint "eagle-import:TO220-5KC")
      (libsource (lib "eagle-import") (part "LM2941K"))
    )
    (comp (ref "C42")
      (value "0.1uF")
      (footprint "eagle-import:C025-024X044")
      (libsource (lib "eagle-import") (part "C-US025-024X044"))
    )
    (comp (ref "C43")
      (value "0.1uF")
      (footprint "eagle-import:C025-024X044")
      (libsource (lib "eagle-import") (part "C-US025-024X044"))
    )
    (comp (ref "J10")
      (value "2524-")
      (footprint "eagle-import:PAK100_2500-24")
      (libsource (lib "eagle-import") (part "2524-"))
    )
    (comp (ref "LCD1")
      (value "HD44780LCD-1602")
      (footprint "eagle-import:LCD1602")
      (libsource (lib "eagle-import") (part "HD44780LCD-1602"))
    )
    (comp (ref "LED1")
      (value "OUTPUT A")
      (footprint "eagle-import:LED5MM")
      (libsource (lib "eagle-import") (part "LED5MM"))
    )
    (comp (ref "LED2")
      (value "OUTPUT B")
      (footprint "eagle-import:LED5MM")
      (libsource (lib "eagle-import") (part "LED5MM"))
    )
    (comp (ref "LED3")
      (value "RADIO")
      (footprint "eagle-import:LED5MM")
      (libsource (lib "eagle-import") (part "LED5MM"))
    )
    (comp (ref "LED4")
      (value "POWER")
      (footprint "eagle-import:LED5MM")
      (libsource (lib "eagle-import") (part "LED5MM"))
    )
    (comp (ref "Q7")
      (value "2N3904")
      (footprint "eagle-import:TO92")
      (libsource (lib "eagle-import") (part "2N3904"))
    )
    (comp (ref "Q8")
      (value "2N3904")
      (footprint "eagle-import:TO92")
      (libsource (lib "eagle-import") (part "2N3904"))
    )
    (comp (ref "R53")
      (value "390")
      (footprint "eagle-import:0207_10")
      (libsource (lib "eagle-import") (part "R-US_0207/10"))
    )
    (comp (ref "R54")
      (value "390")
      (footprint "eagle-import:0207_10")
      (libsource (lib "eagle-import") (part "R-US_0207/10"))
    )
    (comp (ref "R55")
      (value "47")
      (footprint "eagle-import:0207_10")
      (libsource (lib "eagle-import") (part "R-US_0207/10"))
    )
    (comp (ref "R56")
      (value "1.5K")
      (footprint "eagle-import:0207_10")
      (libsource (lib "eagle-import") (part "R-US_0207/10"))
    )
    (comp (ref "R57")
      (value "1.5K")
      (footprint "eagle-import:0207_10")
      (libsource (lib "eagle-import") (part "R-US_0207/10"))
    )
    (comp (ref "R59")
      (value "390")
      (footprint "eagle-import:0207_10")
      (libsource (lib "eagle-import") (part "R-US_0207/10"))
    )
    (comp (ref "R60")
      (value "390")
      (footprint "eagle-import:0207_10")
      (libsource (lib "eagle-import") (part "R-US_0207/10"))
    )
    (comp (ref "S1")
      (value "OK")
      (footprint "eagle-import:DTE6K")
      (libsource (lib "eagle-import") (part "DTE6K"))
    )
    (comp (ref "S2")
      (value "MENU")
      (footprint "eagle-import:DTE6K")
      (libsource (lib "eagle-import") (part "DTE6K"))
    )
    (comp (ref "S3")
      (value "LEFT/DOWN")
      (footprint "eagle-import:DTE6K")
      (libsource (lib "eagle-import") (part "DTE6K"))
    )
    (comp (ref "S4")
      (value "RIGHT/UP")
      (footprint "eagle-import:DTE6K")
      (libsource (lib "eagle-import") (part "DTE6K"))
    )
    (comp (ref "U3")
      (value "4066N")
      (footprint "eagle-import:DIL14")
      (libsource (lib "eagle-import") (part "4066N"))
    )
    (comp (ref "VR1")
      (value "LEVEL A")
      (footprint "eagle-import:9MM_SNAP-IN_POT")
      (libsource (lib "eagle-import") (part "9MM_SNAP-IN_POT_CHASSIS"))
    )
    (comp (ref "VR2")
      (value "LEVEL B")
      (footprint "eagle-import:9MM_SNAP-IN_POT")
      (libsource (lib "eagle-import") (part "9MM_SNAP-IN_POT_CHASSIS"))
    )
    (comp (ref "VR3")
      (value "MULTI-ADJ")
      (footprint "eagle-import:DUAL_9MM_SNAP-IN_POT")
      (libsource (lib "eagle-import") (part "ALPHA-9MM-DUALPOT"))
    )
    (comp (ref "VR4")
      (value "LCD CONTRAST")
      (footprint "eagle-import:B25P")
      (libsource (lib "eagle-import") (part "TRIM_US-B25P"))
    )
  )
  (nets
    (net (code "1") (name "+5V") (class "Default")
      (node (ref "C10") (pin "1") (pinfunction "1_1") (pintype "passive"))
      (node (ref "C17") (pin "1") (pinfunction "1_1") (pintype "passive"))
      (node (ref "C18") (pin "1") (pinfunction "1_1") (pintype "passive"))
      (node (ref "C19") (pin "1") (pinfunction "1_1") (pintype "passive"))
      (node (ref "C29") (pin "1") (pinfunction "1_1") (pintype "passive"))
      (node (ref "C32") (pin "1") (pinfunction "1_1") (pintype "passive"))
      (node (ref "C33") (pin "1") (pinfunction "1_1") (pintype "passive"))
      (node (ref "C37") (pin "1") (pinfunction "1_1") (pintype "passive"))
      (node (ref "C41") (pin "1") (pinfunction "1_1") (pintype "passive"))
      (node (ref "C42") (pin "1") (pinfunction "1_1") (pintype "passive"))
      (node (ref "C43") (pin "1") (pinfunction "1_1") (pintype "passive"))
      (node (ref "C44") (pin "1") (pinfunction "1_1") (pintype "passive"))
      (node (ref "C8") (pin "+") (pinfunction "+_+") (pintype "passive"))
      (node (ref "J10") (pin "19") (pinfunction "KL_19") (pintype "passive"))
      (node (ref "J10") (pin "20") (pinfunction "KL_20") (pintype "passive"))
      (node (ref "J11") (pin "19") (pinfunction "KL_19") (pintype "passive"))
      (node (ref "J11") (pin "20") (pinfunction "KL_20") (pintype "passive"))
      (node (ref "J9") (pin "5") (pinfunction "5_5") (pintype "passive"))
      (node (ref "JP1") (pin "2") (pinfunction "S_2") (pintype "passive"))
      (node (ref "LCD1") (pin "2") (pinfunction "VDD_2") (pintype "power_in"))
      (node (ref "R16") (pin "2") (pinfunction "2_2") (pintype "passive"))
      (node (ref "R17") (pin "2") (pinfunction "2_2") (pintype "passive"))
      (node (ref "R18") (pin "2") (pinfunction "2_2") (pintype "passive"))
      (node (ref "R26") (pin "2") (pinfunction "2_2") (pintype "passive"))
      (node (ref "R34") (pin "2") (pinfunction "2_2") (pintype "passive"))
      (node (ref "R45") (pin "2") (pinfunction "2_2") (pintype "passive"))
      (node (ref "R53") (pin "2") (pinfunction "2_2") (pintype "passive"))
      (node (ref "R54") (pin "2") (pinfunction "2_2") (pintype "passive"))
      (node (ref "R55") (pin "2") (pinfunction "2_2") (pintype "passive"))
      (node (ref "R57") (pin "1") (pinfunction "1_1") (pintype "passive"))
      (node (ref "R60") (pin "2") (pinfunction "2_2") (pintype "passive"))
      (node (ref "R8") (pin "2") (pinfunction "2_2") (pintype "passive"))
      (node (ref "U1") (pin "10") (pinfunction "VCC_10") (pintype "power_in"))
      (node (ref "U1") (pin "30") (pinfunction "AVCC_30") (pintype "power_in"))
      (node (ref "U1") (pin "32") (pinfunction "AREF_32") (pintype "passive"))
      (node (ref "U13") (pin "3") (pinfunction "VO_3") (pintype "passive"))
      (node (ref "U2") (pin "4") (pinfunction "V+_4") (pintype "power_in"))
      (node (ref "U3") (pin "14") (pinfunction "VDD_14") (pintype "power_in"))
      (node (ref "U4") (pin "8") (pinfunction "V+_8") (pintype "power_in"))
      (node (ref "U8A") (pin "6") (pinfunction "~{LDAC}_6") (pintype "bidirectional"))
      (node (ref "U8A") (pin "8") (pinfunction "VDD_8") (pintype "bidirectional"))
      (node (ref "U8B") (pin "4") (pinfunction "4_4") (pintype "passive"))
      (node (ref "U8B") (pin "6") (pinfunction "6_6") (pintype "passive"))
      (node (ref "U9") (pin "16") (pinfunction "VCC_16") (pintype "power_in"))
      (node (ref "VR1") (pin "3") (pinfunction "E_3") (pintype "passive"))
      (node (ref "VR2") (pin "3") (pinfunction "E_3") (pintype "passive"))
      (node (ref "VR4") (pin "E") (pinfunction "E_E") (pintype "passive"))
    )
    (net (code "2") (name "+8V") (class "Default")
      (node (ref "C12") (pin "1") (pinfunction "1_1") (pintype "passive"))
      (node (ref "C38") (pin "1") (pinfunction "1_1") (pintype "passive"))
      (node (ref "C39") (pin "2") (pinfunction "2_2") (pintype "passive"))
      (node (ref "C6") (pin "+") (pinfunction "+_+") (pintype "passive"))
      (node (ref "Q3") (pin "3") (pinfunction "S_3") (pintype "passive"))
      (node (ref "R32") (pin "2") (pinfunction "2_2") (pintype "passive"))
      (node (ref "U10") (pin "8") (pinfunction "V+_8") (pintype "power_in"))
      (node (ref "U11") (pin "3") (pinfunction "VO_3") (pintype "passive"))
    )
    (net (code "3") (name "+9V") (class "Default")
      (node (ref "C14") (pin "1") (pinfunction "1_1") (pintype "passive"))
      (node (ref "C40") (pin "2") (pinfunction "2_2") (pintype "passive"))
      (node (ref "C7") (pin "+") (pinfunction "+_+") (pintype "passive"))
      (node (ref "Q6") (pin "3") (pinfunction "S_3") (pintype "passive"))
      (node (ref "R43") (pin "2") (pinfunction "2_2") (pintype "passive"))
      (node (ref "U12") (pin "3") (pinfunction "VO_3") (pintype "passive"))
    )
    (net (code "4") (name "+12V") (class "Default")
      (node (ref "C11") (pin "1") (pinfunction "1_1") (pintype "passive"))
      (node (ref "C13") (pin "1") (pinfunction "1_1") (pintype "passive"))
      (node (ref "C9") (pin "1") (pinfunction "1_1") (pintype "passive"))
      (node (ref "R5") (pin "2") (pinfunction "2_2") (pintype "passive"))
      (node (ref "S5") (pin "1") (pinfunction "O_1") (pintype "passive"))
      (node (ref "U11") (pin "1") (pinfunction "VI_1") (pintype "input"))
      (node (ref "U12") (pin "1") (pinfunction "VI_1") (pintype "input"))
      (node (ref "U13") (pin "1") (pinfunction "VI_1") (pintype "input"))
    )
    (net (code "5") (name "GND") (class "Default")
      (node (ref "C1") (pin "-") (pinfunction "-_-") (pintype "passive"))
      (node (ref "C10") (pin "2") (pinfunction "2_2") (pintype "passive"))
      (node (ref "C11") (pin "2") (pinfunction "2_2") (pintype "passive"))
      (node (ref "C12") (pin "2") (pinfunction "2_2") (pintype "passive"))
      (node (ref "C13") (pin "2") (pinfunction "2_2") (pintype "passive"))
      (node (ref "C14") (pin "2") (pinfunction "2_2") (pintype "passive"))
      (node (ref "C15") (pin "2") (pinfunction "2_2") (pintype "passive"))
      (node (ref "C16") (pin "2") (pinfunction "2_2") (pintype "passive"))
      (node (ref "C17") (pin "2") (pinfunction "2_2") (pintype "passive"))
      (node (ref "C18") (pin "2") (pinfunction "2_2") (pintype "passive"))
      (node (ref "C19") (pin "2") (pinfunction "2_2") (pintype "passive"))
      (node (ref "C2") (pin "2") (pinfunction "2_2") (pintype "passive"))
      (node (ref "C20") (pin "2") (pinfunction "2_2") (pintype "passive"))
      (node (ref "C25") (pin "2") (pinfunction "2_2") (pintype "passive"))
      (node (ref "C27") (pin "2") (pinfunction "2_2") (pintype "passive"))
      (node (ref "C29") (pin "2") (pinfunction "2_2") (pintype "passive"))
      (node (ref "C3") (pin "2") (pinfunction "2_2") (pintype "passive"))
      (node (ref "C30") (pin "2") (pinfunction "2_2") (pintype "passive"))
      (node (ref "C31") (pin "2") (pinfunction "2_2") (pintype "passive"))
      (node (ref "C32") (pin "2") (pinfunction "2_2") (pintype "passive"))
      (node (ref "C34") (pin "2") (pinfunction "2_2") (pintype "passive"))
      (node (ref "C37") (pin "2") (pinfunction "2_2") (pintype "passive"))
      (node (ref "C38") (pin "2") (pinfunction "2_2") (pintype "passive"))
      (node (ref "C4") (pin "-") (pinfunction "-_-") (pintype "passive"))
      (node (ref "C41") (pin "2") (pinfunction "2_2") (pintype "passive"))
      (node (ref "C42") (pin "2") (pinfunction "2_2") (pintype "passive"))
      (node (ref "C43") (pin "2") (pinfunction "2_2") (pintype "passive"))
      (node (ref "C44") (pin "2") (pinfunction "2_2") (pintype "passive"))
      (node (ref "C5") (pin "-") (pinfunction "-_-") (pintype "passive"))
      (node (ref "C6") (pin "-") (pinfunction "-_-") (pintype "passive"))
      (node (ref "C7") (pin "-") (pinfunction "-_-") (pintype "passive"))
      (node (ref "C8") (pin "-") (pinfunction "-_-") (pintype "passive"))
      (node (ref "C9") (pin "2") (pinfunction "2_2") (pintype "passive"))
      (node (ref "J1") (pin "-") (pinfunction "-_-") (pintype "passive"))
      (node (ref "J10") (pin "21") (pinfunction "KL_21") (pintype "passive"))
      (node (ref "J10") (pin "22") (pinfunction "KL_22") (pintype "passive"))
      (node (ref "J10") (pin "23") (pinfunction "KL_23") (pintype "passive"))
      (node (ref "J10") (pin "24") (pinfunction "KL_24") (pintype "passive"))
      (node (ref "J11") (pin "21") (pinfunction "KL_21") (pintype "passive"))
      (node (ref "J11") (pin "22") (pinfunction "KL_22") (pintype "passive"))
      (node (ref "J11") (pin "23") (pinfunction "KL_23") (pintype "passive"))
      (node (ref "J11") (pin "24") (pinfunction "KL_24") (pintype "passive"))
      (node (ref "J2") (pin "1") (pinfunction "1_1") (pintype "passive"))
      (node (ref "J3") (pin "1") (pinfunction "1_1") (pintype "passive"))
      (node (ref "J4") (pin "1") (pinfunction "1_1") (pintype "passive"))
      (node (ref "J5") (pin "1") (pinfunction "1_1") (pintype "passive"))
      (node (ref "J8") (pin "GND@1") (pinfunction "GNDBREAK_GND@1") (pintype "bidirectional"))
      (node (ref "J8") (pin "GND@2") (pinfunction "GND_GND@2") (pintype "bidirectional"))
      (node (ref "J9") (pin "4") (pinfunction "4_4") (pintype "passive"))
      (node (ref "JP1") (pin "6") (pinfunction "S_6") (pintype "passive"))
      (node (ref "LCD1") (pin "1") (pinfunction "VSS_1") (pintype "power_in"))
      (node (ref "LED4") (pin "K") (pinfunction "C_K") (pintype "passive"))
      (node (ref "Q7") (pin "3") (pinfunction "E_3") (pintype "passive"))
      (node (ref "Q8") (pin "3") (pinfunction "E_3") (pintype "passive"))
      (node (ref "R10") (pin "1") (pinfunction "1_1") (pintype "passive"))
      (node (ref "R11") (pin "1") (pinfunction "1_1") (pintype "passive"))
      (node (ref "R19") (pin "1") (pinfunction "1_1") (pintype "passive"))
      (node (ref "R2") (pin "1") (pinfunction "1_1") (pintype "passive"))
      (node (ref "R20") (pin "1") (pinfunction "1_1") (pintype "passive"))
      (node (ref "R21") (pin "1") (pinfunction "1_1") (pintype "passive"))
      (node (ref "R22") (pin "1") (pinfunction "1_1") (pintype "passive"))
      (node (ref "R24") (pin "2") (pinfunction "2_2") (pintype "passive"))
      (node (ref "R27") (pin "2") (pinfunction "2_2") (pintype "passive"))
      (node (ref "R28") (pin "2") (pinfunction "2_2") (pintype "passive"))
      (node (ref "R29") (pin "2") (pinfunction "2_2") (pintype "passive"))
      (node (ref "R30") (pin "1") (pinfunction "1_1") (pintype "passive"))
      (node (ref "R33") (pin "1") (pinfunction "1_1") (pintype "passive"))
      (node (ref "R35") (pin "1") (pinfunction "1_1") (pintype "passive"))
      (node (ref "R37") (pin "1") (pinfunction "1_1") (pintype "passive"))
      (node (ref "R4") (pin "1") (pinfunction "1_1") (pintype "passive"))
      (node (ref "R40") (pin "1") (pinfunction "1_1") (pintype "passive"))
      (node (ref "R44") (pin "1") (pinfunction "1_1") (pintype "passive"))
      (node (ref "R46") (pin "1") (pinfunction "1_1") (pintype "passive"))
      (node (ref "R48") (pin "1") (pinfunction "1_1") (pintype "passive"))
      (node (ref "R51") (pin "1") (pinfunction "1_1") (pintype "passive"))
      (node (ref "R58") (pin "1") (pinfunction "1_1") (pintype "passive"))
      (node (ref "R59") (pin "2") (pinfunction "2_2") (pintype "passive"))
      (node (ref "R6") (pin "1") (pinfunction "1_1") (pintype "passive"))
      (node (ref "S1") (pin "3") (pinfunction "P_3") (pintype "passive"))
      (node (ref "S1") (pin "4") (pinfunction "P_4") (pintype "passive"))
      (node (ref "S2") (pin "3") (pinfunction "P_3") (pintype "passive"))
      (node (ref "S2") (pin "4") (pinfunction "P_4") (pintype "passive"))
      (node (ref "S3") (pin "3") (pinfunction "P_3") (pintype "passive"))
      (node (ref "S3") (pin "4") (pinfunction "P_4") (pintype "passive"))
      (node (ref "S4") (pin "3") (pinfunction "P_3") (pintype "passive"))
      (node (ref "S4") (pin "4") (pinfunction "P_4") (pintype "passive"))
      (node (ref "S5") (pin "B") (pinfunction "B_B") (pintype "passive"))
      (node (ref "S5") (pin "B1") (pinfunction "B1_B1") (pintype "passive"))
      (node (ref "U1") (pin "11") (pinfunction "GND_11") (pintype "power_in"))
      (node (ref "U1") (pin "31") (pinfunction "GND_31") (pintype "power_in"))
      (node (ref "U10") (pin "4") (pinfunction "V-_4") (pintype "power_in"))
      (node (ref "U11") (pin "2") (pinfunction "GND_2") (pintype "passive"))
      (node (ref "U12") (pin "2") (pinfunction "GND_2") (pintype "passive"))
      (node (ref "U13") (pin "2") (pinfunction "GND_2") (pintype "passive"))
      (node (ref "U14") (pin "2") (pinfunction "~{ON}/OFF_2") (pintype "input"))
      (node (ref "U14") (pin "3") (pinfunction "GND_3") (pintype "power_in"))
      (node (ref "U2") (pin "11") (pinfunction "V-_11") (pintype "power_in"))
      (node (ref "U3") (pin "7") (pinfunction "VSS_7") (pintype "power_in"))
      (node (ref "U4") (pin "4") (pinfunction "V-_4") (pintype "power_in"))
      (node (ref "U4") (pin "5") (pinfunction "+IN_5") (pintype "input"))
      (node (ref "U8A") (pin "1") (pinfunction "GND_1") (pintype "bidirectional"))
      (node (ref "U8B") (pin "7") (pinfunction "7_7") (pintype "passive"))
      (node (ref "U9") (pin "15") (pinfunction "GND_15") (pintype "power_in"))
      (node (ref "VR1") (pin "1") (pinfunction "A_1") (pintype "passive"))
      (node (ref "VR1") (pin "CHASSIS2") (pinfunction "P$1_CHASSIS2") (pintype "passive"))
      (node (ref "VR2") (pin "1") (pinfunction "A_1") (pintype "passive"))
      (node (ref "VR2") (pin "CHASSIS2") (pinfunction "P$1_CHASSIS2") (pintype "passive"))
      (node (ref "VR3") (pin "1") (pinfunction "A_1") (pintype "passive"))
      (node (ref "VR3") (pin "1B") (pinfunction "A_1B") (pintype "passive"))
      (node (ref "VR3") (pin "CHASSIS1") (pinfunction "P$1_CHASSIS1") (pintype "passive"))
      (node (ref "VR3") (pin "CHASSIS2") (pinfunction "P$1_CHASSIS2") (pintype "passive"))
      (node (ref "VR4") (pin "A") (pinfunction "A_A") (pintype "passive"))
    )
    (net (code "6") (name "Net-(C20-Pad1)") (class "Default")
      (node (ref "C20") (pin "1") (pinfunction "1_1") (pintype "passive"))
      (node (ref "C21") (pin "1") (pinfunction "1_1") (pintype "passive"))
      (node (ref "R7") (pin "2") (pinfunction "2_2") (pintype "passive"))
      (node (ref "R8") (pin "1") (pinfunction "1_1") (pintype "passive"))
    )
    (net (code "7") (name "Net-(C22-Pad2)") (class "Default")
      (node (ref "C22") (pin "2") (pinfunction "2_2") (pintype "passive"))
      (node (ref "R13") (pin "2") (pinfunction "2_2") (pintype "passive"))
    )
    (net (code "8") (name "Net-(C23-Pad1)") (class "Default")
      (node (ref "C23") (pin "1") (pinfunction "1_1") (pintype "passive"))
      (node (ref "R14") (pin "2") (pinfunction "2_2") (pintype "passive"))
    )
    (net (code "9") (name "Net-(C24-Pad1)") (class "Default")
      (node (ref "C24") (pin "1") (pinfunction "1_1") (pintype "passive"))
      (node (ref "R15") (pin "2") (pinfunction "2_2") (pintype "passive"))
    )
    (net (code "10") (name "Net-(F1-Pad1)") (class "Default")
      (node (ref "F1") (pin "1") (pinfunction "1_1") (pintype "passive"))
      (node (ref "J1") (pin "+") (pinfunction "+_+") (pintype "passive"))
    )
    (net (code "11") (name "Net-(J2-Pad2)") (class "Default")
      (node (ref "J2") (pin "2") (pinfunction "2_2") (pintype "passive"))
      (node (ref "R18") (pin "1") (pinfunction "1_1") (pintype "passive"))
      (node (ref "R19") (pin "2") (pinfunction "2_2") (pintype "passive"))
    )
    (net (code "12") (name "Net-(J4-Pad2)") (class "Default")
      (node (ref "J4") (pin "2") (pinfunction "2_2") (pintype "passive"))
      (node (ref "J4") (pin "5") (pinfunction "5_5") (pintype "passive"))
      (node (ref "R7") (pin "1") (pinfunction "1_1") (pintype "passive"))
    )
    (net (code "13") (name "Net-(J5-Pad2)") (class "Default")
      (node (ref "J5") (pin "2") (pinfunction "2_2") (pintype "passive"))
      (node (ref "R15") (pin "1") (pinfunction "1_1") (pintype "passive"))
    )
    (net (code "14") (name "Net-(J5-Pad5)") (class "Default")
      (node (ref "J5") (pin "5") (pinfunction "5_5") (pintype "passive"))
      (node (ref "R14") (pin "1") (pinfunction "1_1") (pintype "passive"))
    )
    (net (code "15") (name "Net-(J6-Pad1)") (class "Default")
      (node (ref "J6") (pin "1") (pinfunction "1_1") (pintype "passive"))
      (node (ref "TR1") (pin "4") (pinfunction "4_4") (pintype "passive"))
    )
    (net (code "16") (name "Net-(J6-Pad2)") (class "Default")
      (node (ref "J6") (pin "2") (pinfunction "2_2") (pintype "passive"))
      (node (ref "JP6") (pin "2") (pinfunction "2_2") (pintype "passive"))
    )
    (net (code "17") (name "Net-(J6-Pad5)") (class "Default")
      (node (ref "J6") (pin "5") (pinfunction "5_5") (pintype "passive"))
      (node (ref "TR1") (pin "6") (pinfunction "6_6") (pintype "passive"))
    )
    (net (code "18") (name "Net-(J7-Pad1)") (class "Default")
      (node (ref "J7") (pin "1") (pinfunction "1_1") (pintype "passive"))
      (node (ref "TR2") (pin "4") (pinfunction "4_4") (pintype "passive"))
    )
    (net (code "19") (name "Net-(J7-Pad2)") (class "Default")
      (node (ref "J7") (pin "2") (pinfunction "2_2") (pintype "passive"))
      (node (ref "JP7") (pin "2") (pinfunction "2_2") (pintype "passive"))
    )
    (net (code "20") (name "Net-(J7-Pad5)") (class "Default")
      (node (ref "J7") (pin "5") (pinfunction "5_5") (pintype "passive"))
      (node (ref "TR2") (pin "6") (pinfunction "6_6") (pintype "passive"))
    )
    (net (code "21") (name "Net-(J9-Pad2)") (class "Default")
      (node (ref "J9") (pin "2") (pinfunction "2_2") (pintype "passive"))
      (node (ref "R58") (pin "2") (pinfunction "2_2") (pintype "passive"))
      (node (ref "R9") (pin "1") (pinfunction "1_1") (pintype "passive"))
    )
    (net (code "22") (name "Net-(J10A-KL)") (class "Default")
      (node (ref "J10") (pin "1") (pinfunction "KL_1") (pintype "passive"))
      (node (ref "VR3") (pin "3") (pinfunction "E_3") (pintype "passive"))
    )
    (net (code "23") (name "Net-(J10C-KL)") (class "Default")
      (node (ref "J10") (pin "11") (pinfunction "KL_11") (pintype "passive"))
      (node (ref "VR2") (pin "2") (pinfunction "S_2") (pintype "passive"))
    )
    (net (code "24") (name "Net-(J10I-KL)") (class "Default")
      (node (ref "J10") (pin "17") (pinfunction "KL_17") (pintype "passive"))
      (node (ref "LED3") (pin "A") (pinfunction "A_A") (pintype "passive"))
    )
    (net (code "25") (name "Net-(J10R-KL)") (class "Default")
      (node (ref "J10") (pin "3") (pinfunction "KL_3") (pintype "passive"))
      (node (ref "VR3") (pin "3B") (pinfunction "E_3B") (pintype "passive"))
    )
    (net (code "26") (name "Net-(J10T-KL)") (class "Default")
      (node (ref "J10") (pin "5") (pinfunction "KL_5") (pintype "passive"))
      (node (ref "VR3") (pin "2") (pinfunction "S_2") (pintype "passive"))
    )
    (net (code "27") (name "Net-(J10V-KL)") (class "Default")
      (node (ref "J10") (pin "7") (pinfunction "KL_7") (pintype "passive"))
      (node (ref "VR3") (pin "2B") (pinfunction "S_2B") (pintype "passive"))
    )
    (net (code "28") (name "Net-(J10X-KL)") (class "Default")
      (node (ref "J10") (pin "9") (pinfunction "KL_9") (pintype "passive"))
      (node (ref "VR1") (pin "2") (pinfunction "S_2") (pintype "passive"))
    )
    (net (code "29") (name "Net-(JP6-Pad1)") (class "Default")
      (node (ref "JP6") (pin "1") (pinfunction "1_1") (pintype "passive"))
      (node (ref "TR1") (pin "5") (pinfunction "5_5") (pintype "passive"))
    )
    (net (code "30") (name "Net-(JP7-Pad1)") (class "Default")
      (node (ref "JP7") (pin "1") (pinfunction "1_1") (pintype "passive"))
      (node (ref "TR2") (pin "5") (pinfunction "5_5") (pintype "passive"))
    )
    (net (code "31") (name "Net-(LCD1-A)") (class "Default")
      (node (ref "LCD1") (pin "15") (pinfunction "A_15") (pintype "input"))
      (node (ref "R55") (pin "1") (pinfunction "1_1") (pintype "passive"))
    )
    (net (code "32") (name "Net-(LCD1-K)") (class "Default")
      (node (ref "LCD1") (pin "16") (pinfunction "K_16") (pintype "input"))
      (node (ref "Q8") (pin "1") (pinfunction "C_1") (pintype "passive"))
    )
    (net (code "33") (name "Net-(LCD1-VO)") (class "Default")
      (node (ref "LCD1") (pin "3") (pinfunction "VO_3") (pintype "input"))
      (node (ref "VR4") (pin "S") (pinfunction "S_S") (pintype "passive"))
    )
    (net (code "34") (name "Net-(LED1-PadA)") (class "Default")
      (node (ref "LED1") (pin "A") (pinfunction "A_A") (pintype "passive"))
      (node (ref "R54") (pin "1") (pinfunction "1_1") (pintype "passive"))
    )
    (net (code "35") (name "Net-(LED2-PadA)") (class "Default")
      (node (ref "LED2") (pin "A") (pinfunction "A_A") (pintype "passive"))
      (node (ref "R53") (pin "1") (pinfunction "1_1") (pintype "passive"))
    )
    (net (code "36") (name "Net-(LED3-C)") (class "Default")
      (node (ref "LED3") (pin "K") (pinfunction "C_K") (pintype "passive"))
      (node (ref "R59") (pin "1") (pinfunction "1_1") (pintype "passive"))
    )
    (net (code "37") (name "Net-(LED4-PadA)") (class "Default")
      (node (ref "LED4") (pin "A") (pinfunction "A_A") (pintype "passive"))
      (node (ref "R60") (pin "1") (pinfunction "1_1") (pintype "passive"))
    )
    (net (code "38") (name "Net-(Q1-D)") (class "Default")
      (node (ref "Q1") (pin "2") (pinfunction "D_2") (pintype "passive"))
      (node (ref "TR1") (pin "1") (pinfunction "1_1") (pintype "passive"))
    )
    (net (code "39") (name "Net-(Q1-G)") (class "Default")
      (node (ref "Q1") (pin "1") (pinfunction "G_1") (pintype "passive"))
      (node (ref "R38") (pin "2") (pinfunction "2_2") (pintype "passive"))
    )
    (net (code "40") (name "Net-(Q2-D)") (class "Default")
      (node (ref "Q2") (pin "2") (pinfunction "D_2") (pintype "passive"))
      (node (ref "TR1") (pin "3") (pinfunction "3_3") (pintype "passive"))
    )
    (net (code "41") (name "Net-(Q2-G)") (class "Default")
      (node (ref "Q2") (pin "1") (pinfunction "G_1") (pintype "passive"))
      (node (ref "R41") (pin "2") (pinfunction "2_2") (pintype "passive"))
    )
    (net (code "42") (name "Net-(Q3-D)") (class "Default")
      (node (ref "Q3") (pin "2") (pinfunction "D_2") (pintype "passive"))
      (node (ref "TR1") (pin "2") (pinfunction "2_2") (pintype "passive"))
    )
    (net (code "43") (name "Net-(Q3-G)") (class "Default")
      (node (ref "C39") (pin "1") (pinfunction "1_1") (pintype "passive"))
      (node (ref "Q3") (pin "1") (pinfunction "G_1") (pintype "passive"))
      (node (ref "R39") (pin "2") (pinfunction "2_2") (pintype "passive"))
    )
    (net (code "44") (name "Net-(Q4-D)") (class "Default")
      (node (ref "Q4") (pin "2") (pinfunction "D_2") (pintype "passive"))
      (node (ref "TR2") (pin "1") (pinfunction "1_1") (pintype "passive"))
    )
    (net (code "45") (name "Net-(Q4-G)") (class "Default")
      (node (ref "Q4") (pin "1") (pinfunction "G_1") (pintype "passive"))
      (node (ref "R49") (pin "2") (pinfunction "2_2") (pintype "passive"))
    )
    (net (code "46") (name "Net-(Q5-D)") (class "Default")
      (node (ref "Q5") (pin "2") (pinfunction "D_2") (pintype "passive"))
      (node (ref "TR2") (pin "3") (pinfunction "3_3") (pintype "passive"))
    )
    (net (code "47") (name "Net-(Q5-G)") (class "Default")
      (node (ref "Q5") (pin "1") (pinfunction "G_1") (pintype "passive"))
      (node (ref "R52") (pin "2") (pinfunction "2_2") (pintype "passive"))
    )
    (net (code "48") (name "Net-(Q6-D)") (class "Default")
      (node (ref "Q6") (pin "2") (pinfunction "D_2") (pintype "passive"))
      (node (ref "TR2") (pin "2") (pinfunction "2_2") (pintype "passive"))
    )
    (net (code "49") (name "Net-(Q6-G)") (class "Default")
      (node (ref "C40") (pin "1") (pinfunction "1_1") (pintype "passive"))
      (node (ref "Q6") (pin "1") (pinfunction "G_1") (pintype "passive"))
      (node (ref "R50") (pin "2") (pinfunction "2_2") (pintype "passive"))
    )
    (net (code "50") (name "Net-(Q7-B)") (class "Default")
      (node (ref "Q7") (pin "2") (pinfunction "B_2") (pintype "passive"))
      (node (ref "R56") (pin "1") (pinfunction "1_1") (pintype "passive"))
    )
    (net (code "51") (name "Net-(Q7-C)") (class "Default")
      (node (ref "Q7") (pin "1") (pinfunction "C_1") (pintype "passive"))
      (node (ref "Q8") (pin "2") (pinfunction "B_2") (pintype "passive"))
      (node (ref "R57") (pin "2") (pinfunction "2_2") (pintype "passive"))
    )
    (net (code "52") (name "Net-(S5-P)") (class "Default")
      (node (ref "C5") (pin "+") (pinfunction "+_+") (pintype "passive"))
      (node (ref "D1") (pin "C") (pinfunction "C_C") (pintype "passive"))
      (node (ref "F1") (pin "2") (pinfunction "2_2") (pintype "passive"))
      (node (ref "S5") (pin "2") (pinfunction "P_2") (pintype "passive"))
      (node (ref "S5") (pin "3") (pinfunction "S_3") (pintype "passive"))
    )
    (net (code "53") (name "Net-(U1-(ADC2)PA2)") (class "Default")
      (node (ref "R3") (pin "1") (pinfunction "1_1") (pintype "passive"))
      (node (ref "R4") (pin "2") (pinfunction "2_2") (pintype "passive"))
      (node (ref "U1") (pin "38") (pinfunction "(ADC2)PA2_38") (pintype "bidirectional"))
    )
    (net (code "54") (name "Net-(U1-(ADC3)PA3)") (class "Default")
      (node (ref "R5") (pin "1") (pinfunction "1_1") (pintype "passive"))
      (node (ref "R6") (pin "2") (pinfunction "2_2") (pintype "passive"))
      (node (ref "U1") (pin "37") (pinfunction "(ADC3)PA3_37") (pintype "bidirectional"))
    )
    (net (code "55") (name "Net-(U1-XTAL1)") (class "Default")
      (node (ref "C16") (pin "1") (pinfunction "1_1") (pintype "passive"))
      (node (ref "U1") (pin "13") (pinfunction "XTAL1_13") (pintype "bidirectional"))
      (node (ref "XTAL1") (pin "2") (pinfunction "2_2") (pintype "passive"))
    )
    (net (code "56") (name "Net-(U1-XTAL2)") (class "Default")
      (node (ref "C15") (pin "1") (pinfunction "1_1") (pintype "passive"))
      (node (ref "U1") (pin "12") (pinfunction "XTAL2_12") (pintype "bidirectional"))
      (node (ref "XTAL1") (pin "1") (pinfunction "1_1") (pintype "passive"))
    )
    (net (code "57") (name "Net-(U2A-+IN)") (class "Default")
      (node (ref "C28") (pin "2") (pinfunction "2_2") (pintype "passive"))
      (node (ref "J2") (pin "5") (pinfunction "5_5") (pintype "passive"))
      (node (ref "R21") (pin "2") (pinfunction "2_2") (pintype "passive"))
      (node (ref "U2") (pin "3") (pinfunction "+IN_3") (pintype "input"))
    )
    (net (code "58") (name "Net-(U2A--IN)") (class "Default")
      (node (ref "R24") (pin "1") (pinfunction "1_1") (pintype "passive"))
      (node (ref "R25") (pin "1") (pinfunction "1_1") (pintype "passive"))
      (node (ref "U2") (pin "2") (pinfunction "-IN_2") (pintype "input"))
    )
    (net (code "59") (name "Net-(U2A-OUT)") (class "Default")
      (node (ref "D2") (pin "A") (pinfunction "A_A") (pintype "passive"))
      (node (ref "R25") (pin "2") (pinfunction "2_2") (pintype "passive"))
      (node (ref "U2") (pin "1") (pinfunction "OUT_1") (pintype "output"))
      (node (ref "U2") (pin "12") (pinfunction "+IN_12") (pintype "input"))
    )
    (net (code "60") (name "Net-(U2B-+IN)") (class "Default")
      (node (ref "C26") (pin "2") (pinfunction "2_2") (pintype "passive"))
      (node (ref "R20") (pin "2") (pinfunction "2_2") (pintype "passive"))
      (node (ref "U2") (pin "5") (pinfunction "+IN_5") (pintype "input"))
    )
    (net (code "61") (name "Net-(U2B--IN)") (class "Default")
      (node (ref "R22") (pin "2") (pinfunction "2_2") (pintype "passive"))
      (node (ref "R23") (pin "1") (pinfunction "1_1") (pintype "passive"))
      (node (ref "U2") (pin "6") (pinfunction "-IN_6") (pintype "input"))
    )
    (net (code "62") (name "Net-(U2B-OUT)") (class "Default")
      (node (ref "D3") (pin "A") (pinfunction "A_A") (pintype "passive"))
      (node (ref "R23") (pin "2") (pinfunction "2_2") (pintype "passive"))
      (node (ref "U2") (pin "10") (pinfunction "+IN_10") (pintype "input"))
      (node (ref "U2") (pin "7") (pinfunction "OUT_7") (pintype "output"))
    )
    (net (code "63") (name "Net-(U2C--IN)") (class "Default")
      (node (ref "R26") (pin "1") (pinfunction "1_1") (pintype "passive"))
      (node (ref "R27") (pin "1") (pinfunction "1_1") (pintype "passive"))
      (node (ref "U2") (pin "13") (pinfunction "-IN_13") (pintype "input"))
      (node (ref "U2") (pin "9") (pinfunction "-IN_9") (pintype "input"))
    )
    (net (code "64") (name "Net-(U3A-A)") (class "Default")
      (node (ref "S2") (pin "1") (pinfunction "S_1") (pintype "passive"))
      (node (ref "S2") (pin "2") (pinfunction "S_2") (pintype "passive"))
      (node (ref "U3") (pin "1") (pinfunction "A_1") (pintype "tri_state"))
    )
    (net (code "65") (name "Net-(U3B-A)") (class "Default")
      (node (ref "S4") (pin "1") (pinfunction "S_1") (pintype "passive"))
      (node (ref "S4") (pin "2") (pinfunction "S_2") (pintype "passive"))
      (node (ref "U3") (pin "4") (pinfunction "A_4") (pintype "tri_state"))
    )
    (net (code "66") (name "Net-(U3C-A)") (class "Default")
      (node (ref "S1") (pin "1") (pinfunction "S_1") (pintype "passive"))
      (node (ref "S1") (pin "2") (pinfunction "S_2") (pintype "passive"))
      (node (ref "U3") (pin "8") (pinfunction "A_8") (pintype "tri_state"))
    )
    (net (code "67") (name "Net-(U3D-A)") (class "Default")
      (node (ref "S3") (pin "1") (pinfunction "S_1") (pintype "passive"))
      (node (ref "S3") (pin "2") (pinfunction "S_2") (pintype "passive"))
      (node (ref "U3") (pin "11") (pinfunction "A_11") (pintype "tri_state"))
    )
    (net (code "68") (name "Net-(U4A-+IN)") (class "Default")
      (node (ref "C21") (pin "2") (pinfunction "2_2") (pintype "passive"))
      (node (ref "R10") (pin "2") (pinfunction "2_2") (pintype "passive"))
      (node (ref "U4") (pin "3") (pinfunction "+IN_3") (pintype "input"))
    )
    (net (code "69") (name "Net-(U4A--IN)") (class "Default")
      (node (ref "R11") (pin "2") (pinfunction "2_2") (pintype "passive"))
      (node (ref "R12") (pin "1") (pinfunction "1_1") (pintype "passive"))
      (node (ref "U4") (pin "2") (pinfunction "-IN_2") (pintype "input"))
    )
    (net (code "70") (name "Net-(U4A-OUT)") (class "Default")
      (node (ref "R12") (pin "2") (pinfunction "2_2") (pintype "passive"))
      (node (ref "R13") (pin "1") (pinfunction "1_1") (pintype "passive"))
      (node (ref "U4") (pin "1") (pinfunction "OUT_1") (pintype "output"))
      (node (ref "U4") (pin "6") (pinfunction "-IN_6") (pintype "input"))
    )
    (net (code "71") (name "Net-(U8A-OUTA)") (class "Default")
      (node (ref "R31") (pin "1") (pinfunction "1_1") (pintype "passive"))
      (node (ref "U8A") (pin "2") (pinfunction "OUTA_2") (pintype "bidirectional"))
      (node (ref "U8B") (pin "5") (pinfunction "5_5") (pintype "passive"))
    )
    (net (code "72") (name "Net-(U8A-OUTB)") (class "Default")
      (node (ref "R42") (pin "1") (pinfunction "1_1") (pintype "passive"))
      (node (ref "U8A") (pin "7") (pinfunction "OUTB_7") (pintype "bidirectional"))
      (node (ref "U8B") (pin "8") (pinfunction "8_8") (pintype "passive"))
    )
    (net (code "73") (name "Net-(U9A-C1+)") (class "Default")
      (node (ref "C35") (pin "1") (pinfunction "1_1") (pintype "passive"))
      (node (ref "U9") (pin "1") (pinfunction "C1+_1") (pintype "bidirectional"))
    )
    (net (code "74") (name "Net-(U9A-C1-)") (class "Default")
      (node (ref "C35") (pin "2") (pinfunction "2_2") (pintype "passive"))
      (node (ref "U9") (pin "3") (pinfunction "C1-_3") (pintype "bidirectional"))
    )
    (net (code "75") (name "Net-(U9A-C2+)") (class "Default")
      (node (ref "C36") (pin "1") (pinfunction "1_1") (pintype "passive"))
      (node (ref "U9") (pin "4") (pinfunction "C2+_4") (pintype "bidirectional"))
    )
    (net (code "76") (name "Net-(U9A-C2-)") (class "Default")
      (node (ref "C36") (pin "2") (pinfunction "2_2") (pintype "passive"))
      (node (ref "U9") (pin "5") (pinfunction "C2-_5") (pintype "bidirectional"))
    )
    (net (code "77") (name "Net-(U9A-R1IN)") (class "Default")
      (node (ref "J3") (pin "2") (pinfunction "2_2") (pintype "passive"))
      (node (ref "U9") (pin "13") (pinfunction "R1IN_13") (pintype "input"))
    )
    (net (code "78") (name "Net-(U9A-R2IN)") (class "Default")
      (node (ref "J3") (pin "4") (pinfunction "4_4") (pintype "passive"))
      (node (ref "U9") (pin "8") (pinfunction "R2IN_8") (pintype "input"))
    )
    (net (code "79") (name "Net-(U9A-R2OUT)") (class "Default")
      (node (ref "R9") (pin "2") (pinfunction "2_2") (pintype "passive"))
      (node (ref "U9") (pin "9") (pinfunction "R2OUT_9") (pintype "output"))
    )
    (net (code "80") (name "Net-(U9A-T1OUT)") (class "Default")
      (node (ref "J3") (pin "5") (pinfunction "5_5") (pintype "passive"))
      (node (ref "U9") (pin "14") (pinfunction "T1OUT_14") (pintype "output"))
    )
    (net (code "81") (name "Net-(U9A-T2IN)") (class "Default")
      (node (ref "J9") (pin "3") (pinfunction "3_3") (pintype "passive"))
      (node (ref "U9") (pin "10") (pinfunction "T2IN_10") (pintype "input"))
    )
    (net (code "82") (name "Net-(U9A-T2OUT)") (class "Default")
      (node (ref "J3") (pin "3") (pinfunction "3_3") (pintype "passive"))
      (node (ref "U9") (pin "7") (pinfunction "T2OUT_7") (pintype "output"))
    )
    (net (code "83") (name "Net-(U9A-V+)") (class "Default")
      (node (ref "C33") (pin "2") (pinfunction "2_2") (pintype "passive"))
      (node (ref "U9") (pin "2") (pinfunction "V+_2") (pintype "bidirectional"))
    )
    (net (code "84") (name "Net-(U9A-V-)") (class "Default")
      (node (ref "C34") (pin "1") (pinfunction "1_1") (pintype "passive"))
      (node (ref "U9") (pin "6") (pinfunction "V-_6") (pintype "bidirectional"))
    )
    (net (code "85") (name "Net-(U10A-+IN)") (class "Default")
      (node (ref "R31") (pin "2") (pinfunction "2_2") (pintype "passive"))
      (node (ref "R32") (pin "1") (pinfunction "1_1") (pintype "passive"))
      (node (ref "R33") (pin "2") (pinfunction "2_2") (pintype "passive"))
      (node (ref "U10") (pin "3") (pinfunction "+IN_3") (pintype "input"))
    )
    (net (code "86") (name "Net-(U10A--IN)") (class "Default")
      (node (ref "R34") (pin "1") (pinfunction "1_1") (pintype "passive"))
      (node (ref "R35") (pin "2") (pinfunction "2_2") (pintype "passive"))
      (node (ref "R36") (pin "1") (pinfunction "1_1") (pintype "passive"))
      (node (ref "U10") (pin "2") (pinfunction "-IN_2") (pintype "input"))
    )
    (net (code "87") (name "Net-(U10A-OUT)") (class "Default")
      (node (ref "R36") (pin "2") (pinfunction "2_2") (pintype "passive"))
      (node (ref "R39") (pin "1") (pinfunction "1_1") (pintype "passive"))
      (node (ref "U10") (pin "1") (pinfunction "OUT_1") (pintype "output"))
    )
    (net (code "88") (name "Net-(U10B-+IN)") (class "Default")
      (node (ref "R42") (pin "2") (pinfunction "2_2") (pintype "passive"))
      (node (ref "R43") (pin "1") (pinfunction "1_1") (pintype "passive"))
      (node (ref "R44") (pin "2") (pinfunction "2_2") (pintype "passive"))
      (node (ref "U10") (pin "5") (pinfunction "+IN_5") (pintype "input"))
    )
    (net (code "89") (name "Net-(U10B--IN)") (class "Default")
      (node (ref "R45") (pin "1") (pinfunction "1_1") (pintype "passive"))
      (node (ref "R46") (pin "2") (pinfunction "2_2") (pintype "passive"))
      (node (ref "R47") (pin "1") (pinfunction "1_1") (pintype "passive"))
      (node (ref "U10") (pin "6") (pinfunction "-IN_6") (pintype "input"))
    )
    (net (code "90") (name "Net-(U10B-OUT)") (class "Default")
      (node (ref "R47") (pin "2") (pinfunction "2_2") (pintype "passive"))
      (node (ref "R50") (pin "1") (pinfunction "1_1") (pintype "passive"))
      (node (ref "U10") (pin "7") (pinfunction "OUT_7") (pintype "output"))
    )
    (net (code "91") (name "Net-(U14-ADJ)") (class "Default")
      (node (ref "R1") (pin "1") (pinfunction "1_1") (pintype "passive"))
      (node (ref "R2") (pin "2") (pinfunction "2_2") (pintype "passive"))
      (node (ref "U14") (pin "1") (pinfunction "ADJ_1") (pintype "passive"))
    )
    (net (code "92") (name "Net-(U14-OUT)") (class "Default")
      (node (ref "C3") (pin "1") (pinfunction "1_1") (pintype "passive"))
      (node (ref "C4") (pin "+") (pinfunction "+_+") (pintype "passive"))
      (node (ref "D1") (pin "A") (pinfunction "A_A") (pintype "passive"))
      (node (ref "R1") (pin "2") (pinfunction "2_2") (pintype "passive"))
      (node (ref "U14") (pin "5") (pinfunction "OUT_5") (pintype "passive"))
    )
    (net (code "93") (name "PA0") (class "Default")
      (node (ref "Q1") (pin "3") (pinfunction "S_3") (pintype "passive"))
      (node (ref "Q2") (pin "3") (pinfunction "S_3") (pintype "passive"))
      (node (ref "Q4") (pin "3") (pinfunction "S_3") (pintype "passive"))
      (node (ref "Q5") (pin "3") (pinfunction "S_3") (pintype "passive"))
      (node (ref "R30") (pin "2") (pinfunction "2_2") (pintype "passive"))
      (node (ref "U1") (pin "40") (pinfunction "(ADC0)PA0_40") (pintype "bidirectional"))
    )
    (net (code "94") (name "PA1") (class "Default")
      (node (ref "C25") (pin "1") (pinfunction "1_1") (pintype "passive"))
      (node (ref "C26") (pin "1") (pinfunction "1_1") (pintype "passive"))
      (node (ref "J11") (pin "5") (pinfunction "KL_5") (pintype "passive"))
      (node (ref "U1") (pin "39") (pinfunction "(ADC1)PA1_39") (pintype "bidirectional"))
    )
    (net (code "95") (name "PA4") (class "Default")
      (node (ref "J11") (pin "9") (pinfunction "KL_9") (pintype "passive"))
      (node (ref "U1") (pin "36") (pinfunction "(ADC4)PA4_36") (pintype "bidirectional"))
    )
    (net (code "96") (name "PA5") (class "Default")
      (node (ref "J11") (pin "11") (pinfunction "KL_11") (pintype "passive"))
      (node (ref "U1") (pin "35") (pinfunction "(ADC5)PA5_35") (pintype "bidirectional"))
    )
    (net (code "97") (name "PA6") (class "Default")
      (node (ref "C31") (pin "1") (pinfunction "1_1") (pintype "passive"))
      (node (ref "D2") (pin "C") (pinfunction "C_C") (pintype "passive"))
      (node (ref "R29") (pin "1") (pinfunction "1_1") (pintype "passive"))
      (node (ref "U1") (pin "34") (pinfunction "(ADC6)PA6_34") (pintype "bidirectional"))
    )
    (net (code "98") (name "PA7") (class "Default")
      (node (ref "C30") (pin "1") (pinfunction "1_1") (pintype "passive"))
      (node (ref "D3") (pin "C") (pinfunction "C_C") (pintype "passive"))
      (node (ref "R28") (pin "1") (pinfunction "1_1") (pintype "passive"))
      (node (ref "U1") (pin "33") (pinfunction "(ADC7)PA7_33") (pintype "bidirectional"))
    )
    (net (code "99") (name "PB0") (class "Default")
      (node (ref "R48") (pin "2") (pinfunction "2_2") (pintype "passive"))
      (node (ref "R49") (pin "1") (pinfunction "1_1") (pintype "passive"))
      (node (ref "U1") (pin "1") (pinfunction "(T0/XCK)PB0_1") (pintype "bidirectional"))
    )
    (net (code "100") (name "PB1") (class "Default")
      (node (ref "R51") (pin "2") (pinfunction "2_2") (pintype "passive"))
      (node (ref "R52") (pin "1") (pinfunction "1_1") (pintype "passive"))
      (node (ref "U1") (pin "2") (pinfunction "(T1)PB1_2") (pintype "bidirectional"))
    )
    (net (code "101") (name "PB2") (class "Default")
      (node (ref "R37") (pin "2") (pinfunction "2_2") (pintype "passive"))
      (node (ref "R38") (pin "1") (pinfunction "1_1") (pintype "passive"))
      (node (ref "U1") (pin "3") (pinfunction "(AIN0/INT2)PB2_3") (pintype "bidirectional"))
    )
    (net (code "102") (name "PB3") (class "Default")
      (node (ref "R40") (pin "2") (pinfunction "2_2") (pintype "passive"))
      (node (ref "R41") (pin "1") (pinfunction "1_1") (pintype "passive"))
      (node (ref "U1") (pin "4") (pinfunction "(AIN1/OC0)PB3_4") (pintype "bidirectional"))
    )
    (net (code "103") (name "PB5") (class "Default")
      (node (ref "JP1") (pin "4") (pinfunction "S_4") (pintype "passive"))
      (node (ref "U1") (pin "6") (pinfunction "(MOSI)PB5_6") (pintype "bidirectional"))
      (node (ref "U8A") (pin "4") (pinfunction "DIN_4") (pintype "bidirectional"))
      (node (ref "U8B") (pin "3") (pinfunction "3_3") (pintype "passive"))
    )
    (net (code "104") (name "PB6") (class "Default")
      (node (ref "JP1") (pin "1") (pinfunction "S_1") (pintype "passive"))
      (node (ref "U1") (pin "7") (pinfunction "(MISO)PB6_7") (pintype "bidirectional"))
    )
    (net (code "105") (name "PB7") (class "Default")
      (node (ref "JP1") (pin "3") (pinfunction "S_3") (pintype "passive"))
      (node (ref "U1") (pin "8") (pinfunction "(SCK)PB7_8") (pintype "bidirectional"))
      (node (ref "U8A") (pin "5") (pinfunction "SCLK_5") (pintype "bidirectional"))
      (node (ref "U8B") (pin "2") (pinfunction "2_2") (pintype "passive"))
    )
    (net (code "106") (name "PC0") (class "Default")
      (node (ref "J10") (pin "2") (pinfunction "KL_2") (pintype "passive"))
      (node (ref "J11") (pin "2") (pinfunction "KL_2") (pintype "passive"))
      (node (ref "U1") (pin "22") (pinfunction "(SCL)PC0_22") (pintype "bidirectional"))
      (node (ref "U3") (pin "12") (pinfunction "C_12") (pintype "input"))
      (node (ref "U3") (pin "13") (pinfunction "C_13") (pintype "input"))
      (node (ref "U3") (pin "5") (pinfunction "C_5") (pintype "input"))
      (node (ref "U3") (pin "6") (pinfunction "C_6") (pintype "input"))
    )
    (net (code "107") (name "PC1") (class "Default")
      (node (ref "J10") (pin "4") (pinfunction "KL_4") (pintype "passive"))
      (node (ref "J11") (pin "4") (pinfunction "KL_4") (pintype "passive"))
      (node (ref "LCD1") (pin "5") (pinfunction "RW_5") (pintype "input"))
      (node (ref "U1") (pin "23") (pinfunction "(SDA)PC1_23") (pintype "bidirectional"))
    )
    (net (code "108") (name "PC2") (class "Default")
      (node (ref "J10") (pin "6") (pinfunction "KL_6") (pintype "passive"))
      (node (ref "J11") (pin "6") (pinfunction "KL_6") (pintype "passive"))
      (node (ref "LCD1") (pin "6") (pinfunction "E_6") (pintype "input"))
      (node (ref "U1") (pin "24") (pinfunction "(TCK)PC2_24") (pintype "bidirectional"))
    )
    (net (code "109") (name "PC3") (class "Default")
      (node (ref "J10") (pin "8") (pinfunction "KL_8") (pintype "passive"))
      (node (ref "J11") (pin "8") (pinfunction "KL_8") (pintype "passive"))
      (node (ref "LCD1") (pin "4") (pinfunction "RS_4") (pintype "input"))
      (node (ref "U1") (pin "25") (pinfunction "(TMS)PC3_25") (pintype "bidirectional"))
    )
    (net (code "110") (name "PC4") (class "Default")
      (node (ref "J10") (pin "10") (pinfunction "KL_10") (pintype "passive"))
      (node (ref "J11") (pin "10") (pinfunction "KL_10") (pintype "passive"))
      (node (ref "LCD1") (pin "11") (pinfunction "DB4_11") (pintype "bidirectional"))
      (node (ref "U1") (pin "26") (pinfunction "(TDO)PC4_26") (pintype "bidirectional"))
      (node (ref "U3") (pin "10") (pinfunction "B_10") (pintype "tri_state"))
    )
    (net (code "111") (name "PC5") (class "Default")
      (node (ref "J10") (pin "12") (pinfunction "KL_12") (pintype "passive"))
      (node (ref "J11") (pin "12") (pinfunction "KL_12") (pintype "passive"))
      (node (ref "LCD1") (pin "12") (pinfunction "DB5_12") (pintype "bidirectional"))
      (node (ref "U1") (pin "27") (pinfunction "(TDI)PC5_27") (pintype "bidirectional"))
      (node (ref "U3") (pin "9") (pinfunction "B_9") (pintype "tri_state"))
    )
    (net (code "112") (name "PC6") (class "Default")
      (node (ref "J10") (pin "14") (pinfunction "KL_14") (pintype "passive"))
      (node (ref "J11") (pin "14") (pinfunction "KL_14") (pintype "passive"))
      (node (ref "LCD1") (pin "13") (pinfunction "DB6_13") (pintype "bidirectional"))
      (node (ref "U1") (pin "28") (pinfunction "(TOSC1)PC6_28") (pintype "bidirectional"))
      (node (ref "U3") (pin "3") (pinfunction "B_3") (pintype "tri_state"))
    )
    (net (code "113") (name "PC7") (class "Default")
      (node (ref "J10") (pin "16") (pinfunction "KL_16") (pintype "passive"))
      (node (ref "J11") (pin "16") (pinfunction "KL_16") (pintype "passive"))
      (node (ref "LCD1") (pin "14") (pinfunction "DB7_14") (pintype "bidirectional"))
      (node (ref "U1") (pin "29") (pinfunction "(TOSC2)PC7_29") (pintype "bidirectional"))
      (node (ref "U3") (pin "2") (pinfunction "B_2") (pintype "tri_state"))
    )
    (net (code "114") (name "PD0") (class "Default")
      (node (ref "U1") (pin "14") (pinfunction "(RXD)PD0_14") (pintype "bidirectional"))
      (node (ref "U9") (pin "12") (pinfunction "R1OUT_12") (pintype "output"))
    )
    (net (code "115") (name "PD1") (class "Default")
      (node (ref "U1") (pin "15") (pinfunction "(TXD)PD1_15") (pintype "bidirectional"))
      (node (ref "U9") (pin "11") (pinfunction "T1IN_11") (pintype "input"))
    )
    (net (code "116") (name "PD2") (class "Default")
      (node (ref "U1") (pin "16") (pinfunction "(INT0)PD2_16") (pintype "bidirectional"))
      (node (ref "U2") (pin "14") (pinfunction "OUT_14") (pintype "output"))
    )
    (net (code "117") (name "PD3") (class "Default")
      (node (ref "U1") (pin "17") (pinfunction "(INT1)PD3_17") (pintype "bidirectional"))
      (node (ref "U2") (pin "8") (pinfunction "OUT_8") (pintype "output"))
    )
    (net (code "118") (name "PD5") (class "Default")
      (node (ref "J10") (pin "15") (pinfunction "KL_15") (pintype "passive"))
      (node (ref "J11") (pin "15") (pinfunction "KL_15") (pintype "passive"))
      (node (ref "LED2") (pin "K") (pinfunction "C_K") (pintype "passive"))
      (node (ref "U1") (pin "19") (pinfunction "(OC1A)PD5_19") (pintype "bidirectional"))
    )
    (net (code "119") (name "PD6") (class "Default")
      (node (ref "J10") (pin "13") (pinfunction "KL_13") (pintype "passive"))
      (node (ref "J11") (pin "13") (pinfunction "KL_13") (pintype "passive"))
      (node (ref "LED1") (pin "K") (pinfunction "C_K") (pintype "passive"))
      (node (ref "U1") (pin "20") (pinfunction "(ICP)PD6_20") (pintype "bidirectional"))
    )
    (net (code "120") (name "PD7") (class "Default")
      (node (ref "J10") (pin "18") (pinfunction "KL_18") (pintype "passive"))
      (node (ref "J11") (pin "18") (pinfunction "KL_18") (pintype "passive"))
      (node (ref "R56") (pin "2") (pinfunction "2_2") (pintype "passive"))
      (node (ref "U1") (pin "21") (pinfunction "(OC2)PD7_21") (pintype "bidirectional"))
    )
    (net (code "121") (name "RB4") (class "Default")
      (node (ref "C27") (pin "1") (pinfunction "1_1") (pintype "passive"))
      (node (ref "C28") (pin "1") (pinfunction "1_1") (pintype "passive"))
      (node (ref "J11") (pin "7") (pinfunction "KL_7") (pintype "passive"))
    )
    (net (code "122") (name "RB9") (class "Default")
      (node (ref "C22") (pin "1") (pinfunction "1_1") (pintype "passive"))
      (node (ref "C24") (pin "2") (pinfunction "2_2") (pintype "passive"))
      (node (ref "J11") (pin "3") (pinfunction "KL_3") (pintype "passive"))
      (node (ref "R17") (pin "1") (pinfunction "1_1") (pintype "passive"))
    )
    (net (code "123") (name "RB10") (class "Default")
      (node (ref "C23") (pin "2") (pinfunction "2_2") (pintype "passive"))
      (node (ref "J11") (pin "1") (pinfunction "KL_1") (pintype "passive"))
      (node (ref "R16") (pin "1") (pinfunction "1_1") (pintype "passive"))
    )
    (net (code "124") (name "RESET") (class "Default")
      (node (ref "JP1") (pin "5") (pinfunction "S_5") (pintype "passive"))
      (node (ref "U1") (pin "9") (pinfunction "RESET_9") (pintype "input"))
    )
    (net (code "125") (name "STATE") (class "Default")
      (node (ref "J11") (pin "17") (pinfunction "KL_17") (pintype "passive"))
      (node (ref "J9") (pin "1") (pinfunction "1_1") (pintype "passive"))
    )
    (net (code "126") (name "V+") (class "Default")
      (node (ref "C1") (pin "+") (pinfunction "+_+") (pintype "passive"))
      (node (ref "C2") (pin "1") (pinfunction "1_1") (pintype "passive"))
      (node (ref "J8") (pin "PWR") (pinfunction "PWR_PWR") (pintype "bidirectional"))
      (node (ref "R3") (pin "2") (pinfunction "2_2") (pintype "passive"))
      (node (ref "U14") (pin "4") (pinfunction "IN_4") (pintype "passive"))
    )
    (net (code "127") (name "unconnected-(J2-Pad3)") (class "Default")
      (node (ref "J2") (pin "3") (pinfunction "3_3") (pintype "passive"))
    )
    (net (code "128") (name "unconnected-(J2-Pad4)") (class "Default")
      (node (ref "J2") (pin "4") (pinfunction "4_4") (pintype "passive"))
    )
    (net (code "129") (name "unconnected-(J4-Pad3)") (class "Default")
      (node (ref "J4") (pin "3") (pinfunction "3_3") (pintype "passive"))
    )
    (net (code "130") (name "unconnected-(J4-Pad4)") (class "Default")
      (node (ref "J4") (pin "4") (pinfunction "4_4") (pintype "passive"))
    )
    (net (code "131") (name "unconnected-(J5-Pad3)") (class "Default")
      (node (ref "J5") (pin "3") (pinfunction "3_3") (pintype "passive"))
    )
    (net (code "132") (name "unconnected-(J5-Pad4)") (class "Default")
      (node (ref "J5") (pin "4") (pinfunction "4_4") (pintype "passive"))
    )
    (net (code "133") (name "unconnected-(J6-Pad3)") (class "Default")
      (node (ref "J6") (pin "3") (pinfunction "3_3") (pintype "passive"))
    )
    (net (code "134") (name "unconnected-(J6-Pad4)") (class "Default")
      (node (ref "J6") (pin "4") (pinfunction "4_4") (pintype "passive"))
    )
    (net (code "135") (name "unconnected-(J7-Pad3)") (class "Default")
      (node (ref "J7") (pin "3") (pinfunction "3_3") (pintype "passive"))
    )
    (net (code "136") (name "unconnected-(J7-Pad4)") (class "Default")
      (node (ref "J7") (pin "4") (pinfunction "4_4") (pintype "passive"))
    )
    (net (code "137") (name "unconnected-(J9-Pad6)") (class "Default")
      (node (ref "J9") (pin "6") (pinfunction "6_6") (pintype "passive"))
    )
    (net (code "138") (name "unconnected-(LCD1-DB0-Pad7)") (class "Default")
      (node (ref "LCD1") (pin "7") (pinfunction "DB0_7") (pintype "bidirectional"))
    )
    (net (code "139") (name "unconnected-(LCD1-DB1-Pad8)") (class "Default")
      (node (ref "LCD1") (pin "8") (pinfunction "DB1_8") (pintype "bidirectional"))
    )
    (net (code "140") (name "unconnected-(LCD1-DB2-Pad9)") (class "Default")
      (node (ref "LCD1") (pin "9") (pinfunction "DB2_9") (pintype "bidirectional"))
    )
    (net (code "141") (name "unconnected-(LCD1-DB3-Pad10)") (class "Default")
      (node (ref "LCD1") (pin "10") (pinfunction "DB3_10") (pintype "bidirectional"))
    )
    (net (code "142") (name "unconnected-(U1-(SS)PB4-Pad5)") (class "Default")
      (node (ref "U1") (pin "5") (pinfunction "(SS)PB4_5") (pintype "bidirectional"))
    )
    (net (code "143") (name "unconnected-(U4B-OUT-Pad7)") (class "Default")
      (node (ref "U4") (pin "7") (pinfunction "OUT_7") (pintype "output"))
    )
    (net (code "144") (name "~{CS}") (class "Default")
      (node (ref "U1") (pin "18") (pinfunction "(OC1B)PD4_18") (pintype "bidirectional"))
      (node (ref "U8A") (pin "3") (pinfunction "~{CS}_3") (pintype "bidirectional"))
      (node (ref "U8B") (pin "1") (pinfunction "1_1") (pintype "passive"))
    )
  )
)
